# V71_XplainedUltra_CAN_Shield.net
KiCad netlist of a schematic drawn in EasyEDA
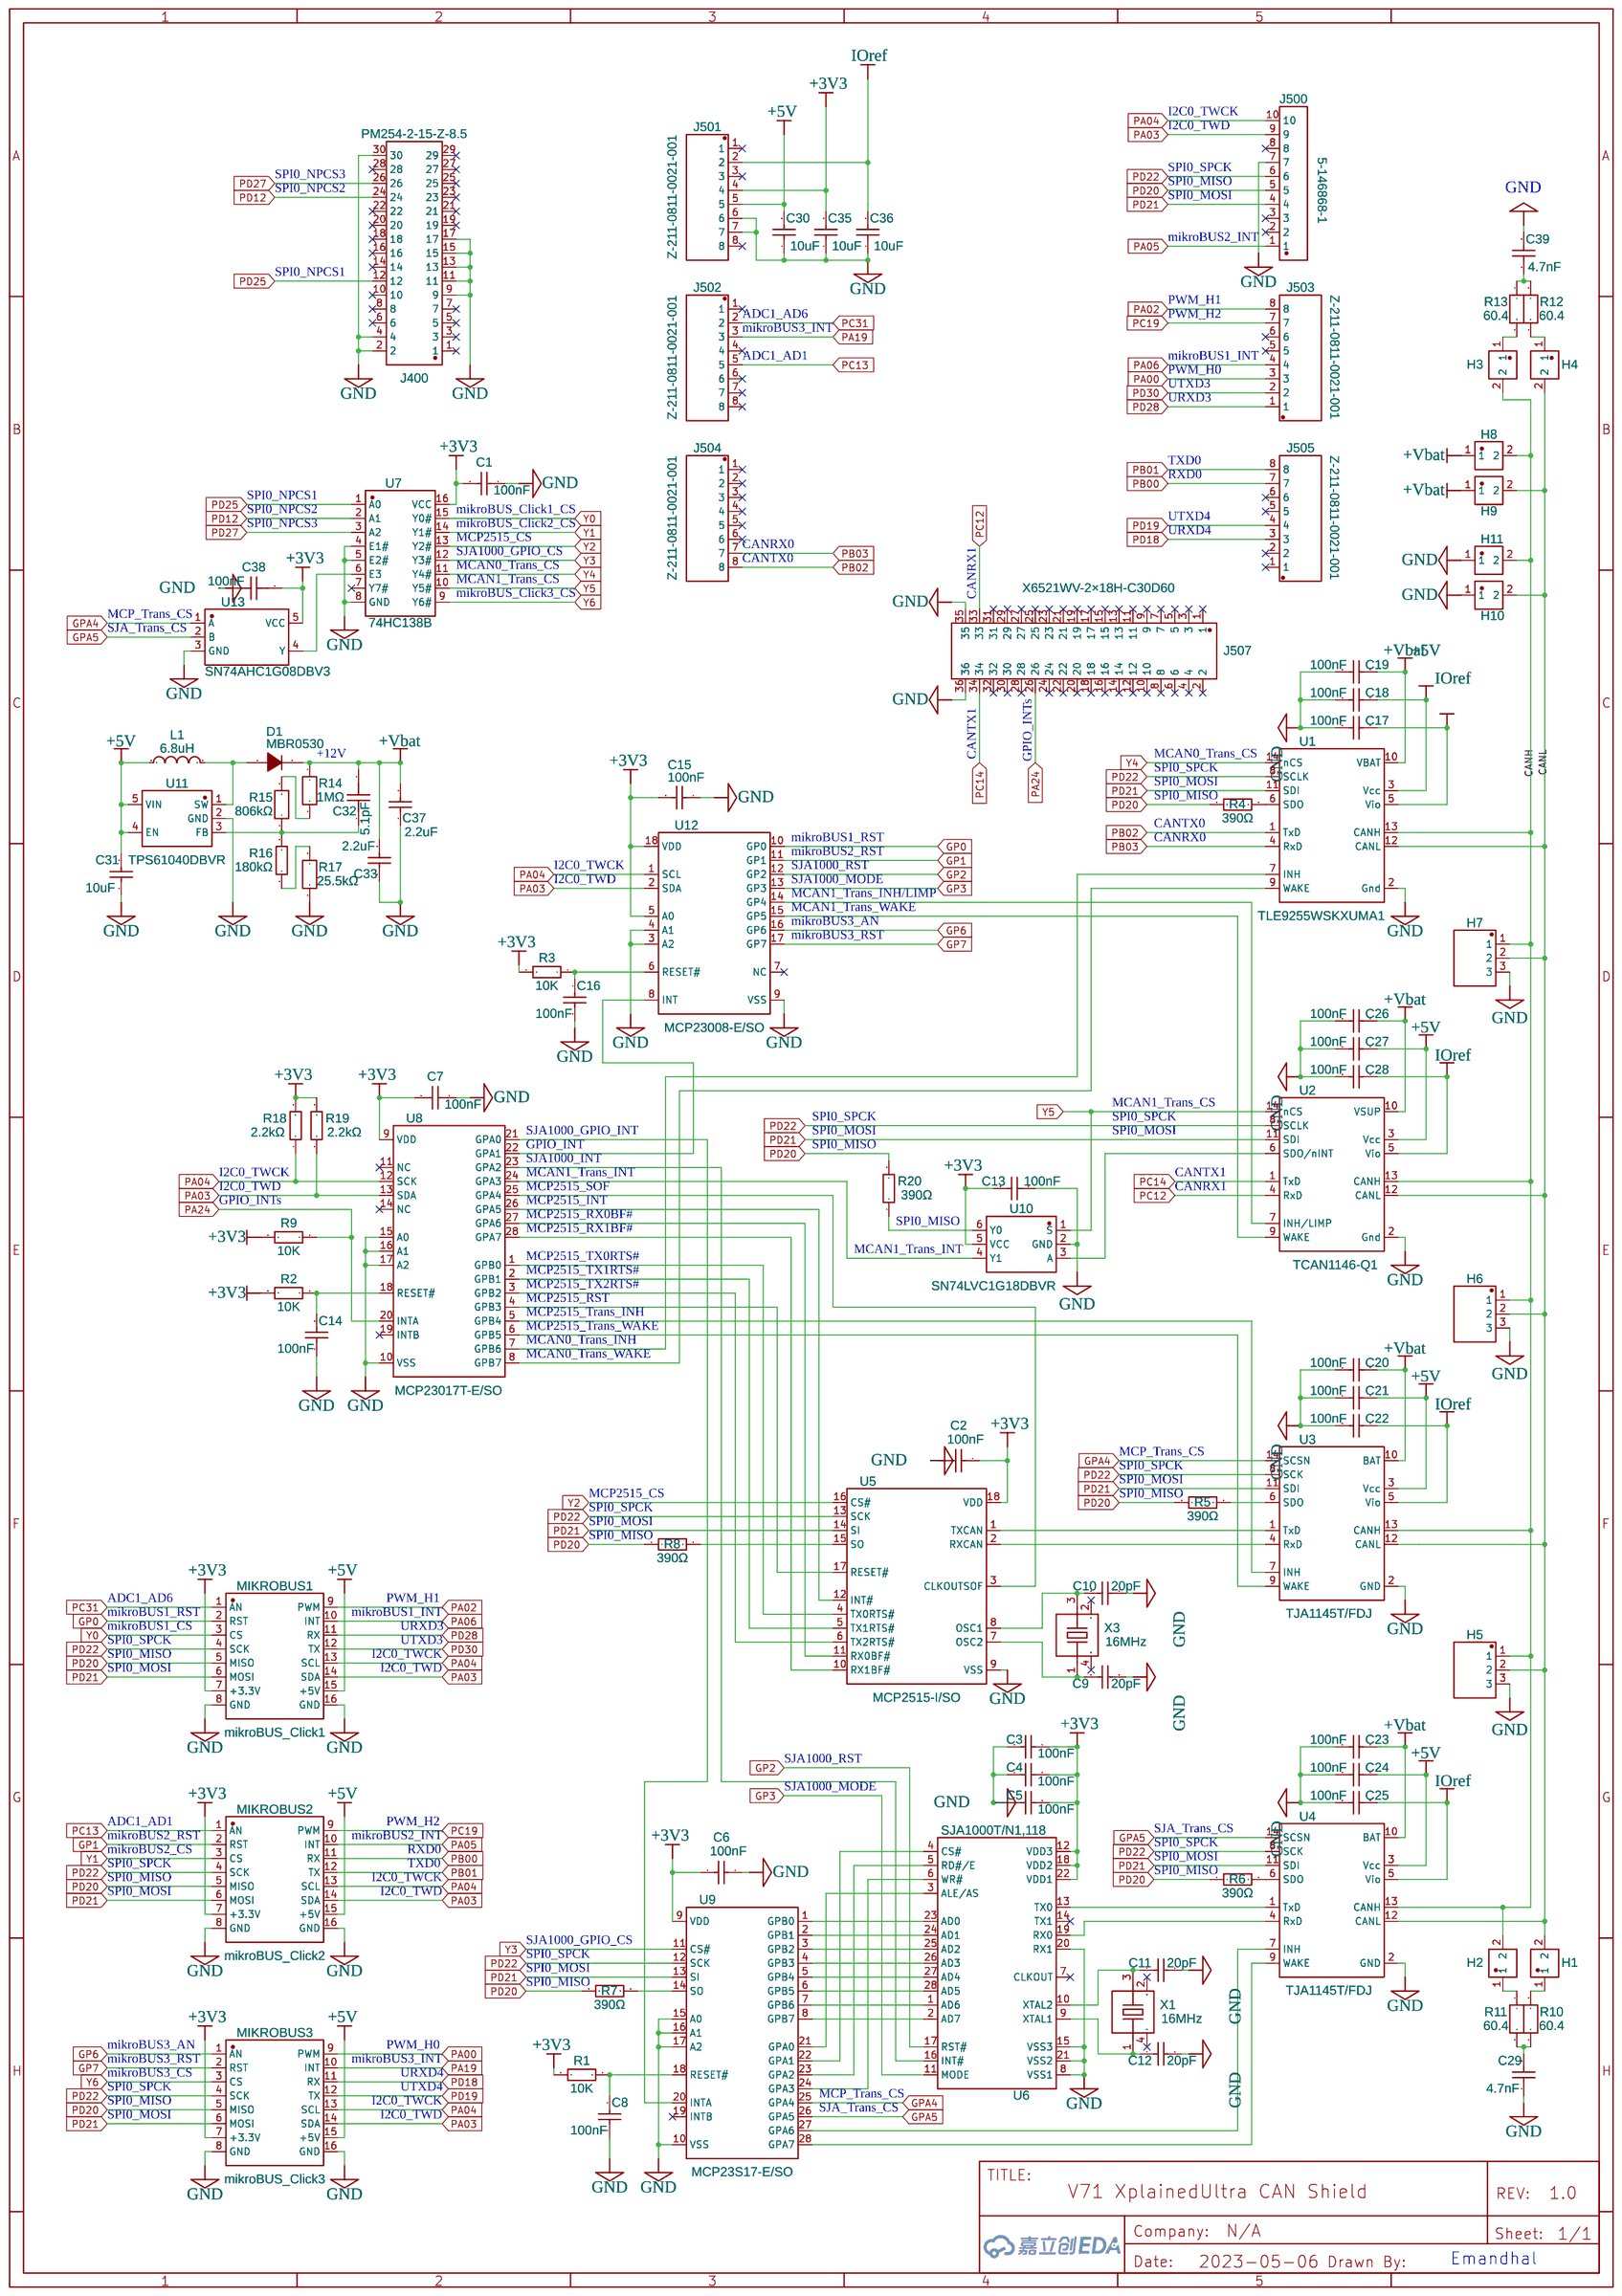
[diagram p0: schematic sheet]

(export (version "E")
  (design (tool "Eeschema 10.0.6"))
  (components
    (comp (ref "C1")
      (value "100nF")
      (fields
        (field (name "Manufacturer Part") "CC0805KRX7R9BB104")
        (field (name "Manufacturer") "YAGEO(国巨)")
      )
      (libsource (lib "") (part "CC0805KRX7R9BB104"))
    )
    (comp (ref "C2")
      (value "100nF")
      (fields
        (field (name "Manufacturer Part") "CC0805KRX7R9BB104")
        (field (name "Manufacturer") "YAGEO(国巨)")
      )
      (libsource (lib "") (part "CC0805KRX7R9BB104"))
    )
    (comp (ref "C3")
      (value "100nF")
      (fields
        (field (name "Manufacturer Part") "CC0805KRX7R9BB104")
        (field (name "Manufacturer") "YAGEO(国巨)")
      )
      (libsource (lib "") (part "CC0805KRX7R9BB104"))
    )
    (comp (ref "C4")
      (value "100nF")
      (fields
        (field (name "Manufacturer Part") "CC0805KRX7R9BB104")
        (field (name "Manufacturer") "YAGEO(国巨)")
      )
      (libsource (lib "") (part "CC0805KRX7R9BB104"))
    )
    (comp (ref "C5")
      (value "100nF")
      (fields
        (field (name "Manufacturer Part") "CC0805KRX7R9BB104")
        (field (name "Manufacturer") "YAGEO(国巨)")
      )
      (libsource (lib "") (part "CC0805KRX7R9BB104"))
    )
    (comp (ref "C6")
      (value "100nF")
      (fields
        (field (name "Manufacturer Part") "CC0805KRX7R9BB104")
        (field (name "Manufacturer") "YAGEO(国巨)")
      )
      (libsource (lib "") (part "CC0805KRX7R9BB104"))
    )
    (comp (ref "C7")
      (value "100nF")
      (fields
        (field (name "Manufacturer Part") "CC0805KRX7R9BB104")
        (field (name "Manufacturer") "YAGEO(国巨)")
      )
      (libsource (lib "") (part "CC0805KRX7R9BB104"))
    )
    (comp (ref "C8")
      (value "100nF")
      (fields
        (field (name "Manufacturer Part") "CC0805KRX7R9BB104")
        (field (name "Manufacturer") "YAGEO(国巨)")
      )
      (libsource (lib "") (part "CC0805KRX7R9BB104_1"))
    )
    (comp (ref "C9")
      (value "20pF")
      (fields
        (field (name "Manufacturer Part") "CL10C200JB8NNNC")
        (field (name "Manufacturer") "SAMSUNG(三星)")
      )
      (libsource (lib "") (part "CL10C200JB8NNNC"))
    )
    (comp (ref "C10")
      (value "20pF")
      (fields
        (field (name "Manufacturer Part") "CL10C200JB8NNNC")
        (field (name "Manufacturer") "SAMSUNG(三星)")
      )
      (libsource (lib "") (part "CL10C200JB8NNNC"))
    )
    (comp (ref "C11")
      (value "20pF")
      (fields
        (field (name "Manufacturer Part") "CL10C200JB8NNNC")
        (field (name "Manufacturer") "SAMSUNG(三星)")
      )
      (libsource (lib "") (part "CL10C200JB8NNNC"))
    )
    (comp (ref "C12")
      (value "20pF")
      (fields
        (field (name "Manufacturer Part") "CL10C200JB8NNNC")
        (field (name "Manufacturer") "SAMSUNG(三星)")
      )
      (libsource (lib "") (part "CL10C200JB8NNNC"))
    )
    (comp (ref "C13")
      (value "100nF")
      (fields
        (field (name "Manufacturer Part") "CC0805KRX7R9BB104")
        (field (name "Manufacturer") "YAGEO(国巨)")
      )
      (libsource (lib "") (part "CC0805KRX7R9BB104"))
    )
    (comp (ref "C14")
      (value "100nF")
      (fields
        (field (name "Manufacturer Part") "CC0805KRX7R9BB104")
        (field (name "Manufacturer") "YAGEO(国巨)")
      )
      (libsource (lib "") (part "CC0805KRX7R9BB104_1"))
    )
    (comp (ref "C15")
      (value "100nF")
      (fields
        (field (name "Manufacturer Part") "CC0805KRX7R9BB104")
        (field (name "Manufacturer") "YAGEO(国巨)")
      )
      (libsource (lib "") (part "CC0805KRX7R9BB104"))
    )
    (comp (ref "C16")
      (value "100nF")
      (fields
        (field (name "Manufacturer Part") "CC0805KRX7R9BB104")
        (field (name "Manufacturer") "YAGEO(国巨)")
      )
      (libsource (lib "") (part "CC0805KRX7R9BB104_1"))
    )
    (comp (ref "C17")
      (value "100nF")
      (fields
        (field (name "Manufacturer Part") "CC0805KRX7R9BB104")
        (field (name "Manufacturer") "YAGEO(国巨)")
      )
      (libsource (lib "") (part "CC0805KRX7R9BB104"))
    )
    (comp (ref "C18")
      (value "100nF")
      (fields
        (field (name "Manufacturer Part") "CC0805KRX7R9BB104")
        (field (name "Manufacturer") "YAGEO(国巨)")
      )
      (libsource (lib "") (part "CC0805KRX7R9BB104"))
    )
    (comp (ref "C19")
      (value "100nF")
      (fields
        (field (name "Manufacturer Part") "CC0805KRX7R9BB104")
        (field (name "Manufacturer") "YAGEO(国巨)")
      )
      (libsource (lib "") (part "CC0805KRX7R9BB104"))
    )
    (comp (ref "C20")
      (value "100nF")
      (fields
        (field (name "Manufacturer Part") "CC0805KRX7R9BB104")
        (field (name "Manufacturer") "YAGEO(国巨)")
      )
      (libsource (lib "") (part "CC0805KRX7R9BB104"))
    )
    (comp (ref "C21")
      (value "100nF")
      (fields
        (field (name "Manufacturer Part") "CC0805KRX7R9BB104")
        (field (name "Manufacturer") "YAGEO(国巨)")
      )
      (libsource (lib "") (part "CC0805KRX7R9BB104"))
    )
    (comp (ref "C22")
      (value "100nF")
      (fields
        (field (name "Manufacturer Part") "CC0805KRX7R9BB104")
        (field (name "Manufacturer") "YAGEO(国巨)")
      )
      (libsource (lib "") (part "CC0805KRX7R9BB104"))
    )
    (comp (ref "C23")
      (value "100nF")
      (fields
        (field (name "Manufacturer Part") "CC0805KRX7R9BB104")
        (field (name "Manufacturer") "YAGEO(国巨)")
      )
      (libsource (lib "") (part "CC0805KRX7R9BB104"))
    )
    (comp (ref "C24")
      (value "100nF")
      (fields
        (field (name "Manufacturer Part") "CC0805KRX7R9BB104")
        (field (name "Manufacturer") "YAGEO(国巨)")
      )
      (libsource (lib "") (part "CC0805KRX7R9BB104"))
    )
    (comp (ref "C25")
      (value "100nF")
      (fields
        (field (name "Manufacturer Part") "CC0805KRX7R9BB104")
        (field (name "Manufacturer") "YAGEO(国巨)")
      )
      (libsource (lib "") (part "CC0805KRX7R9BB104"))
    )
    (comp (ref "C26")
      (value "100nF")
      (fields
        (field (name "Manufacturer Part") "CC0805KRX7R9BB104")
        (field (name "Manufacturer") "YAGEO(国巨)")
      )
      (libsource (lib "") (part "CC0805KRX7R9BB104"))
    )
    (comp (ref "C27")
      (value "100nF")
      (fields
        (field (name "Manufacturer Part") "CC0805KRX7R9BB104")
        (field (name "Manufacturer") "YAGEO(国巨)")
      )
      (libsource (lib "") (part "CC0805KRX7R9BB104"))
    )
    (comp (ref "C28")
      (value "100nF")
      (fields
        (field (name "Manufacturer Part") "CC0805KRX7R9BB104")
        (field (name "Manufacturer") "YAGEO(国巨)")
      )
      (libsource (lib "") (part "CC0805KRX7R9BB104"))
    )
    (comp (ref "C29")
      (value "4.7nF")
      (fields (field (name "Manufacturer Part") "0805B472K500NT") (field (name "Manufacturer") "FH(风华)"))
      (libsource (lib "") (part "0805B472K500NT"))
    )
    (comp (ref "C30")
      (value "10uF")
      (fields
        (field (name "Manufacturer Part") "CL21A106KAYNNNE")
        (field (name "Manufacturer") "SAMSUNG(三星)")
      )
      (libsource (lib "") (part "CL21A106KAYNNNE"))
    )
    (comp (ref "C31")
      (value "10uF")
      (fields
        (field (name "Manufacturer Part") "CL21A106KAYNNNE")
        (field (name "Manufacturer") "SAMSUNG(三星)")
      )
      (libsource (lib "") (part "CL21A106KAYNNNE"))
    )
    (comp (ref "C32")
      (value "5.1pF")
      (fields
        (field (name "Manufacturer Part") "CC0805CRNPO9BN5R1")
        (field (name "Manufacturer") "YAGEO(国巨)")
      )
      (libsource (lib "") (part "CC0805CRNPO9BN5R1"))
    )
    (comp (ref "C33")
      (value "2.2uF")
      (fields (field (name "Manufacturer Part") "0805F225M500NT") (field (name "Manufacturer") "FH(风华)"))
      (libsource (lib "") (part "0805F225M500NT"))
    )
    (comp (ref "C35")
      (value "10uF")
      (fields
        (field (name "Manufacturer Part") "CL21A106KAYNNNE")
        (field (name "Manufacturer") "SAMSUNG(三星)")
      )
      (libsource (lib "") (part "CL21A106KAYNNNE"))
    )
    (comp (ref "C36")
      (value "10uF")
      (fields
        (field (name "Manufacturer Part") "CL21A106KAYNNNE")
        (field (name "Manufacturer") "SAMSUNG(三星)")
      )
      (libsource (lib "") (part "CL21A106KAYNNNE"))
    )
    (comp (ref "C37")
      (value "2.2uF")
      (fields (field (name "Manufacturer Part") "0805F225M500NT") (field (name "Manufacturer") "FH(风华)"))
      (libsource (lib "") (part "0805F225M500NT"))
    )
    (comp (ref "C38")
      (value "100nF")
      (fields
        (field (name "Manufacturer Part") "CC0805KRX7R7BB104")
        (field (name "Manufacturer") "YAGEO(国巨)")
      )
      (libsource (lib "") (part "CC0805KRX7R7BB104"))
    )
    (comp (ref "C39")
      (value "4.7nF")
      (fields (field (name "Manufacturer Part") "0805B472K500NT") (field (name "Manufacturer") "FH(风华)"))
      (libsource (lib "") (part "0805B472K500NT"))
    )
    (comp (ref "D1")
      (value "MBR0530")
      (fields (field (name "Manufacturer") "CJ(江苏长电/长晶)"))
      (libsource (lib "") (part "MBR0530"))
    )
    (comp (ref "H1")
      (value "X6521WV-2X01H-C30D60")
      (fields
        (field (name "Manufacturer Part") "X6521WV-2x01H-C30D60")
        (field (name "Manufacturer") "XKB Connectivity(中国星坤)")
      )
      (libsource (lib "") (part "X6521WV-2X01H-C30D60_2"))
    )
    (comp (ref "H2")
      (value "X6521WV-2X01H-C30D60")
      (fields
        (field (name "Manufacturer Part") "X6521WV-2x01H-C30D60")
        (field (name "Manufacturer") "XKB Connectivity(中国星坤)")
      )
      (libsource (lib "") (part "X6521WV-2X01H-C30D60_2"))
    )
    (comp (ref "H3")
      (value "X6521WV-2X01H-C30D60")
      (fields
        (field (name "Manufacturer Part") "X6521WV-2x01H-C30D60")
        (field (name "Manufacturer") "XKB Connectivity(中国星坤)")
      )
      (libsource (lib "") (part "X6521WV-2X01H-C30D60"))
    )
    (comp (ref "H4")
      (value "X6521WV-2X01H-C30D60")
      (fields
        (field (name "Manufacturer Part") "X6521WV-2x01H-C30D60")
        (field (name "Manufacturer") "XKB Connectivity(中国星坤)")
      )
      (libsource (lib "") (part "X6521WV-2X01H-C30D60"))
    )
    (comp (ref "H5")
      (value "77311-102-03LF")
      (fields (field (name "Manufacturer") "Amphenol"))
      (libsource (lib "") (part "77311-102-03LF"))
    )
    (comp (ref "H6")
      (value "77311-102-03LF")
      (fields (field (name "Manufacturer") "Amphenol"))
      (libsource (lib "") (part "77311-102-03LF"))
    )
    (comp (ref "H7")
      (value "77311-102-03LF")
      (fields (field (name "Manufacturer") "Amphenol"))
      (libsource (lib "") (part "77311-102-03LF"))
    )
    (comp (ref "H8")
      (value "X6521WV-2X01H-C30D60")
      (fields
        (field (name "Manufacturer Part") "X6521WV-2x01H-C30D60")
        (field (name "Manufacturer") "XKB Connectivity(中国星坤)")
      )
      (libsource (lib "") (part "X6521WV-2X01H-C30D60_1"))
    )
    (comp (ref "H9")
      (value "X6521WV-2X01H-C30D60")
      (fields
        (field (name "Manufacturer Part") "X6521WV-2x01H-C30D60")
        (field (name "Manufacturer") "XKB Connectivity(中国星坤)")
      )
      (libsource (lib "") (part "X6521WV-2X01H-C30D60_1"))
    )
    (comp (ref "H10")
      (value "X6521WV-2X01H-C30D60")
      (fields
        (field (name "Manufacturer Part") "X6521WV-2x01H-C30D60")
        (field (name "Manufacturer") "XKB Connectivity(中国星坤)")
      )
      (libsource (lib "") (part "X6521WV-2X01H-C30D60_1"))
    )
    (comp (ref "H11")
      (value "X6521WV-2X01H-C30D60")
      (fields
        (field (name "Manufacturer Part") "X6521WV-2x01H-C30D60")
        (field (name "Manufacturer") "XKB Connectivity(中国星坤)")
      )
      (libsource (lib "") (part "X6521WV-2X01H-C30D60_1"))
    )
    (comp (ref "J400")
      (value "PM254-2-15-Z-8.5")
      (fields (field (name "Manufacturer") "HCTL(华灿天禄)"))
      (libsource (lib "") (part "PM254-2-15-Z-8.5"))
    )
    (comp (ref "J500")
      (value "5-146868-1")
      (fields (field (name "Manufacturer") "TE Connectivity(美国泰科)"))
      (libsource (lib "") (part "5-146868-1"))
    )
    (comp (ref "J501")
      (value "Z-211-0811-0021-001")
      (fields (field (name "Manufacturer") "Nextron(正凌)"))
      (libsource (lib "") (part "Z-211-0811-0021-001"))
    )
    (comp (ref "J502")
      (value "Z-211-0811-0021-001")
      (fields (field (name "Manufacturer") "Nextron(正凌)"))
      (libsource (lib "") (part "Z-211-0811-0021-001"))
    )
    (comp (ref "J503")
      (value "Z-211-0811-0021-001")
      (fields (field (name "Manufacturer") "Nextron(正凌)"))
      (libsource (lib "") (part "Z-211-0811-0021-001_1"))
    )
    (comp (ref "J504")
      (value "Z-211-0811-0021-001")
      (fields (field (name "Manufacturer") "Nextron(正凌)"))
      (libsource (lib "") (part "Z-211-0811-0021-001"))
    )
    (comp (ref "J505")
      (value "Z-211-0811-0021-001")
      (fields (field (name "Manufacturer") "Nextron(正凌)"))
      (libsource (lib "") (part "Z-211-0811-0021-001_1"))
    )
    (comp (ref "J507")
      (value "X6521WV-2×18H-C30D60")
      (fields
        (field (name "Manufacturer Part") "X6521WV-2x18H-C30D60")
        (field (name "Manufacturer") "XKB Connectivity(中国星坤)")
      )
      (libsource (lib "") (part "X6521WV-2×18H-C30D60"))
    )
    (comp (ref "L1")
      (value "6.8uH")
      (fields (field (name "Manufacturer Part") "MLZ2012N6R8LT000") (field (name "Manufacturer") "TDK"))
      (libsource (lib "") (part "MLZ2012N6R8LT000"))
    )
    (comp (ref "MIKROBUS1") (value "mikroBUS_Click1") (libsource (lib "") (part "MIKROE-CLICK-HEADER")))
    (comp (ref "MIKROBUS2") (value "mikroBUS_Click2") (libsource (lib "") (part "MIKROE-CLICK-HEADER")))
    (comp (ref "MIKROBUS3") (value "mikroBUS_Click3") (libsource (lib "") (part "MIKROE-CLICK-HEADER")))
    (comp (ref "R1")
      (value "10K")
      (fields (field (name "Manufacturer Part") "RT0805BRD0710KL") (field (name "Manufacturer") "YAGEO(国巨)"))
      (libsource (lib "") (part "RT0805BRD0710KL"))
    )
    (comp (ref "R2")
      (value "10K")
      (fields (field (name "Manufacturer Part") "RT0805BRD0710KL") (field (name "Manufacturer") "YAGEO(国巨)"))
      (libsource (lib "") (part "RT0805BRD0710KL"))
    )
    (comp (ref "R3")
      (value "10K")
      (fields (field (name "Manufacturer Part") "RT0805BRD0710KL") (field (name "Manufacturer") "YAGEO(国巨)"))
      (libsource (lib "") (part "RT0805BRD0710KL"))
    )
    (comp (ref "R4")
      (value "390Ω")
      (fields
        (field (name "Manufacturer Part") "0805W8F3900T5E")
        (field (name "Manufacturer") "UNI-ROYAL(厚声)")
      )
      (libsource (lib "") (part "0805W8F3900T5E"))
    )
    (comp (ref "R5")
      (value "390Ω")
      (fields
        (field (name "Manufacturer Part") "0805W8F3900T5E")
        (field (name "Manufacturer") "UNI-ROYAL(厚声)")
      )
      (libsource (lib "") (part "0805W8F3900T5E"))
    )
    (comp (ref "R6")
      (value "390Ω")
      (fields
        (field (name "Manufacturer Part") "0805W8F3900T5E")
        (field (name "Manufacturer") "UNI-ROYAL(厚声)")
      )
      (libsource (lib "") (part "0805W8F3900T5E"))
    )
    (comp (ref "R7")
      (value "390Ω")
      (fields
        (field (name "Manufacturer Part") "0805W8F3900T5E")
        (field (name "Manufacturer") "UNI-ROYAL(厚声)")
      )
      (libsource (lib "") (part "0805W8F3900T5E"))
    )
    (comp (ref "R8")
      (value "390Ω")
      (fields
        (field (name "Manufacturer Part") "0805W8F3900T5E")
        (field (name "Manufacturer") "UNI-ROYAL(厚声)")
      )
      (libsource (lib "") (part "0805W8F3900T5E"))
    )
    (comp (ref "R9")
      (value "10K")
      (fields (field (name "Manufacturer Part") "RT0805BRD0710KL") (field (name "Manufacturer") "YAGEO(国巨)"))
      (libsource (lib "") (part "RT0805BRD0710KL"))
    )
    (comp (ref "R10")
      (value "60.4")
      (fields (field (name "Manufacturer Part") "AC0603DR-0760R4L") (field (name "Manufacturer") "YAGEO(国巨)"))
      (libsource (lib "") (part "AC0603DR-0760R4L_1"))
    )
    (comp (ref "R11")
      (value "60.4")
      (fields (field (name "Manufacturer Part") "AC0603DR-0760R4L") (field (name "Manufacturer") "YAGEO(国巨)"))
      (libsource (lib "") (part "AC0603DR-0760R4L"))
    )
    (comp (ref "R12")
      (value "60.4")
      (fields (field (name "Manufacturer Part") "AC0603DR-0760R4L") (field (name "Manufacturer") "YAGEO(国巨)"))
      (libsource (lib "") (part "AC0603DR-0760R4L_1"))
    )
    (comp (ref "R13")
      (value "60.4")
      (fields (field (name "Manufacturer Part") "AC0603DR-0760R4L") (field (name "Manufacturer") "YAGEO(国巨)"))
      (libsource (lib "") (part "AC0603DR-0760R4L"))
    )
    (comp (ref "R14")
      (value "1MΩ")
      (fields (field (name "Manufacturer Part") "CR-05FL7----1M") (field (name "Manufacturer") "Viking(光颉)"))
      (libsource (lib "") (part "CR-05FL7----1M"))
    )
    (comp (ref "R15")
      (value "806kΩ")
      (fields (field (name "Manufacturer Part") "WR08X8063FTL") (field (name "Manufacturer") "Walsin(华新科)"))
      (libsource (lib "") (part "WR08X8063FTL"))
    )
    (comp (ref "R16")
      (value "180kΩ")
      (fields (field (name "Manufacturer Part") "RK73B2ATTD184J") (field (name "Manufacturer") "KOA"))
      (libsource (lib "") (part "RK73B2ATTD184J"))
    )
    (comp (ref "R17")
      (value "25.5kΩ")
      (fields (field (name "Manufacturer Part") "TE05H2552BT") (field (name "Manufacturer") "FH(风华)"))
      (libsource (lib "") (part "TE05H2552BT"))
    )
    (comp (ref "R18")
      (value "2.2kΩ")
      (fields (field (name "Manufacturer Part") "AR05BTB2201") (field (name "Manufacturer") "Viking(光颉)"))
      (libsource (lib "") (part "AR05BTB2201"))
    )
    (comp (ref "R19")
      (value "2.2kΩ")
      (fields (field (name "Manufacturer Part") "AR05BTB2201") (field (name "Manufacturer") "Viking(光颉)"))
      (libsource (lib "") (part "AR05BTB2201"))
    )
    (comp (ref "R20")
      (value "390Ω")
      (fields
        (field (name "Manufacturer Part") "0805W8F3900T5E")
        (field (name "Manufacturer") "UNI-ROYAL(厚声)")
      )
      (libsource (lib "") (part "0805W8F3900T5E_1"))
    )
    (comp (ref "U1")
      (value "TLE9255WSKXUMA1")
      (fields (field (name "Manufacturer") "Infineon(英飞凌)"))
      (libsource (lib "") (part "TLE9255WSKXUMA1"))
    )
    (comp (ref "U2")
      (value "TCAN1146-Q1")
      (fields
        (field (name "Manufacturer Part") "TCAN1146D-Q1")
        (field (name "Manufacturer") "Texas Instruments")
      )
      (libsource (lib "") (part "TCAN1146-Q1"))
    )
    (comp (ref "U3")
      (value "TJA1145T/FDJ")
      (fields (field (name "Manufacturer") "NXP(恩智浦)"))
      (libsource (lib "") (part "TJA1145T/FDJ"))
    )
    (comp (ref "U4")
      (value "TJA1145T/FDJ")
      (fields (field (name "Manufacturer") "NXP(恩智浦)"))
      (libsource (lib "") (part "TJA1145T/FDJ"))
    )
    (comp (ref "U5")
      (value "MCP2515-I/SO")
      (fields (field (name "Manufacturer") "MICROCHIP(美国微芯)"))
      (libsource (lib "") (part "MCP2515-I/SO"))
    )
    (comp (ref "U6")
      (value "SJA1000T/N1,118")
      (fields (field (name "Manufacturer") "NXP(恩智浦)"))
      (libsource (lib "") (part "SJA1000T/N1,118"))
    )
    (comp (ref "U7")
      (value "74HC138B")
      (fields (field (name "Manufacturer") "FM(富满)"))
      (libsource (lib "") (part "74HC138B"))
    )
    (comp (ref "U8")
      (value "MCP23017T-E/SO")
      (fields (field (name "Manufacturer") "MICROCHIP(美国微芯)"))
      (libsource (lib "") (part "MCP23017T-E/SO"))
    )
    (comp (ref "U9")
      (value "MCP23S17-E/SO")
      (fields (field (name "Manufacturer") "MICROCHIP(美国微芯)"))
      (libsource (lib "") (part "MCP23S17-E/SO"))
    )
    (comp (ref "U10")
      (value "SN74LVC1G18DBVR")
      (fields (field (name "Manufacturer") "TI(德州仪器)"))
      (libsource (lib "") (part "SN74LVC1G18DBVR"))
    )
    (comp (ref "U11")
      (value "TPS61040DBVR")
      (fields (field (name "Manufacturer") "TI(德州仪器)"))
      (libsource (lib "") (part "TPS61040DBVR"))
    )
    (comp (ref "U12")
      (value "MCP23008-E/SO")
      (fields (field (name "Manufacturer") "MICROCHIP(美国微芯)"))
      (libsource (lib "") (part "MCP23008-E/SO"))
    )
    (comp (ref "U13")
      (value "SN74AHC1G08DBV3")
      (fields (field (name "Manufacturer") "TI(德州仪器)"))
      (libsource (lib "") (part "SN74AHC1G08DBV3"))
    )
    (comp (ref "X1")
      (value "16MHz")
      (fields
        (field (name "Manufacturer Part") "NX3225SA-16MHz-STD-CSR-6")
        (field (name "Manufacturer") "NDK")
      )
      (libsource (lib "") (part "NX3225SA-16MHZ-STD-CSR-6"))
    )
    (comp (ref "X3")
      (value "16MHz")
      (fields
        (field (name "Manufacturer Part") "NX3225SA-16MHz-STD-CSR-6")
        (field (name "Manufacturer") "NDK")
      )
      (libsource (lib "") (part "NX3225SA-16MHZ-STD-CSR-6"))
    )
  )
  (nets
    (net (code "1") (name "+3V3") (class "Default")
      (node (ref "C1") (pin "2") (pinfunction "2_2") (pintype "input"))
      (node (ref "C13") (pin "2") (pinfunction "2_2") (pintype "input"))
      (node (ref "C15") (pin "2") (pinfunction "2_2") (pintype "input"))
      (node (ref "C2") (pin "1") (pinfunction "1_1") (pintype "input"))
      (node (ref "C3") (pin "1") (pinfunction "1_1") (pintype "input"))
      (node (ref "C35") (pin "2") (pinfunction "2_2") (pintype "input"))
      (node (ref "C38") (pin "1") (pinfunction "1_1") (pintype "unspecified"))
      (node (ref "C4") (pin "1") (pinfunction "1_1") (pintype "input"))
      (node (ref "C5") (pin "1") (pinfunction "1_1") (pintype "input"))
      (node (ref "C6") (pin "2") (pinfunction "2_2") (pintype "input"))
      (node (ref "C7") (pin "2") (pinfunction "2_2") (pintype "input"))
      (node (ref "J501") (pin "4") (pinfunction "4_4") (pintype "unspecified"))
      (node (ref "MIKROBUS1") (pin "7") (pinfunction "+3.3V_7") (pintype "unspecified"))
      (node (ref "MIKROBUS2") (pin "7") (pinfunction "+3.3V_7") (pintype "unspecified"))
      (node (ref "MIKROBUS3") (pin "7") (pinfunction "+3.3V_7") (pintype "unspecified"))
      (node (ref "R1") (pin "2") (pinfunction "2_2") (pintype "input"))
      (node (ref "R18") (pin "2") (pinfunction "2_2") (pintype "unspecified"))
      (node (ref "R19") (pin "2") (pinfunction "2_2") (pintype "unspecified"))
      (node (ref "R2") (pin "2") (pinfunction "2_2") (pintype "input"))
      (node (ref "R3") (pin "2") (pinfunction "2_2") (pintype "input"))
      (node (ref "R9") (pin "2") (pinfunction "2_2") (pintype "input"))
      (node (ref "U10") (pin "5") (pinfunction "VCC_5") (pintype "unspecified"))
      (node (ref "U12") (pin "18") (pinfunction "VDD_18") (pintype "passive"))
      (node (ref "U12") (pin "5") (pinfunction "A0_5") (pintype "input"))
      (node (ref "U13") (pin "5") (pinfunction "VCC_5") (pintype "unspecified"))
      (node (ref "U5") (pin "18") (pinfunction "VDD_18") (pintype "unspecified"))
      (node (ref "U6") (pin "12") (pinfunction "VDD3_12") (pintype "unspecified"))
      (node (ref "U6") (pin "18") (pinfunction "VDD2_18") (pintype "unspecified"))
      (node (ref "U6") (pin "22") (pinfunction "VDD1_22") (pintype "unspecified"))
      (node (ref "U7") (pin "16") (pinfunction "VCC_16") (pintype "unspecified"))
      (node (ref "U8") (pin "9") (pinfunction "VDD_9") (pintype "passive"))
      (node (ref "U9") (pin "9") (pinfunction "VDD_9") (pintype "passive"))
    )
    (net (code "2") (name "+5V") (class "Default")
      (node (ref "C18") (pin "1") (pinfunction "1_1") (pintype "input"))
      (node (ref "C21") (pin "1") (pinfunction "1_1") (pintype "input"))
      (node (ref "C24") (pin "1") (pinfunction "1_1") (pintype "input"))
      (node (ref "C27") (pin "1") (pinfunction "1_1") (pintype "input"))
      (node (ref "C30") (pin "2") (pinfunction "2_2") (pintype "input"))
      (node (ref "C31") (pin "2") (pinfunction "2_2") (pintype "input"))
      (node (ref "J501") (pin "5") (pinfunction "5_5") (pintype "unspecified"))
      (node (ref "L1") (pin "1") (pinfunction "1_1") (pintype "unspecified"))
      (node (ref "MIKROBUS1") (pin "15") (pinfunction "+5V_15") (pintype "unspecified"))
      (node (ref "MIKROBUS2") (pin "15") (pinfunction "+5V_15") (pintype "unspecified"))
      (node (ref "MIKROBUS3") (pin "15") (pinfunction "+5V_15") (pintype "unspecified"))
      (node (ref "U1") (pin "3") (pinfunction "Vcc_3") (pintype "unspecified"))
      (node (ref "U11") (pin "4") (pinfunction "EN_4") (pintype "unspecified"))
      (node (ref "U11") (pin "5") (pinfunction "VIN_5") (pintype "unspecified"))
      (node (ref "U2") (pin "3") (pinfunction "Vcc_3") (pintype "unspecified"))
      (node (ref "U3") (pin "3") (pinfunction "Vcc_3") (pintype "unspecified"))
      (node (ref "U4") (pin "3") (pinfunction "Vcc_3") (pintype "unspecified"))
    )
    (net (code "3") (name "+Vbat") (class "Default")
      (node (ref "C19") (pin "1") (pinfunction "1_1") (pintype "input"))
      (node (ref "C20") (pin "1") (pinfunction "1_1") (pintype "input"))
      (node (ref "C23") (pin "1") (pinfunction "1_1") (pintype "input"))
      (node (ref "C26") (pin "1") (pinfunction "1_1") (pintype "input"))
      (node (ref "C32") (pin "2") (pinfunction "2_2") (pintype "unspecified"))
      (node (ref "C33") (pin "2") (pinfunction "2_2") (pintype "input"))
      (node (ref "C37") (pin "2") (pinfunction "2_2") (pintype "input"))
      (node (ref "D1") (pin "1") (pinfunction "C_1") (pintype "unspecified"))
      (node (ref "H8") (pin "1") (pinfunction "1_1") (pintype "unspecified"))
      (node (ref "H9") (pin "1") (pinfunction "1_1") (pintype "unspecified"))
      (node (ref "R14") (pin "2") (pinfunction "2_2") (pintype "unspecified"))
      (node (ref "U1") (pin "10") (pinfunction "VBAT_10") (pintype "unspecified"))
      (node (ref "U2") (pin "10") (pinfunction "VSUP_10") (pintype "unspecified"))
      (node (ref "U3") (pin "10") (pinfunction "BAT_10") (pintype "unspecified"))
      (node (ref "U4") (pin "10") (pinfunction "BAT_10") (pintype "unspecified"))
    )
    (net (code "4") (name "/CANH") (class "Default")
      (node (ref "H11") (pin "2") (pinfunction "2_2") (pintype "unspecified"))
      (node (ref "H2") (pin "2") (pinfunction "2_2") (pintype "unspecified"))
      (node (ref "H3") (pin "2") (pinfunction "2_2") (pintype "unspecified"))
      (node (ref "H5") (pin "1") (pinfunction "1_1") (pintype "unspecified"))
      (node (ref "H6") (pin "1") (pinfunction "1_1") (pintype "unspecified"))
      (node (ref "H7") (pin "1") (pinfunction "1_1") (pintype "unspecified"))
      (node (ref "H8") (pin "2") (pinfunction "2_2") (pintype "unspecified"))
      (node (ref "U1") (pin "13") (pinfunction "CANH_13") (pintype "unspecified"))
      (node (ref "U2") (pin "13") (pinfunction "CANH_13") (pintype "unspecified"))
      (node (ref "U3") (pin "13") (pinfunction "CANH_13") (pintype "unspecified"))
      (node (ref "U4") (pin "13") (pinfunction "CANH_13") (pintype "unspecified"))
    )
    (net (code "5") (name "/CANL") (class "Default")
      (node (ref "H1") (pin "2") (pinfunction "2_2") (pintype "unspecified"))
      (node (ref "H10") (pin "2") (pinfunction "2_2") (pintype "unspecified"))
      (node (ref "H4") (pin "2") (pinfunction "2_2") (pintype "unspecified"))
      (node (ref "H5") (pin "2") (pinfunction "2_2") (pintype "unspecified"))
      (node (ref "H6") (pin "2") (pinfunction "2_2") (pintype "unspecified"))
      (node (ref "H7") (pin "2") (pinfunction "2_2") (pintype "unspecified"))
      (node (ref "H9") (pin "2") (pinfunction "2_2") (pintype "unspecified"))
      (node (ref "U1") (pin "12") (pinfunction "CANL_12") (pintype "unspecified"))
      (node (ref "U2") (pin "12") (pinfunction "CANL_12") (pintype "unspecified"))
      (node (ref "U3") (pin "12") (pinfunction "CANL_12") (pintype "unspecified"))
      (node (ref "U4") (pin "12") (pinfunction "CANL_12") (pintype "unspecified"))
    )
    (net (code "6") (name "GND") (class "Default")
      (node (ref "C1") (pin "1") (pinfunction "1_1") (pintype "input"))
      (node (ref "C10") (pin "2") (pinfunction "2_2") (pintype "input"))
      (node (ref "C11") (pin "2") (pinfunction "2_2") (pintype "input"))
      (node (ref "C12") (pin "2") (pinfunction "2_2") (pintype "input"))
      (node (ref "C13") (pin "1") (pinfunction "1_1") (pintype "input"))
      (node (ref "C14") (pin "1") (pinfunction "1_1") (pintype "input"))
      (node (ref "C15") (pin "1") (pinfunction "1_1") (pintype "input"))
      (node (ref "C16") (pin "1") (pinfunction "1_1") (pintype "input"))
      (node (ref "C17") (pin "2") (pinfunction "2_2") (pintype "input"))
      (node (ref "C18") (pin "2") (pinfunction "2_2") (pintype "input"))
      (node (ref "C19") (pin "2") (pinfunction "2_2") (pintype "input"))
      (node (ref "C2") (pin "2") (pinfunction "2_2") (pintype "input"))
      (node (ref "C20") (pin "2") (pinfunction "2_2") (pintype "input"))
      (node (ref "C21") (pin "2") (pinfunction "2_2") (pintype "input"))
      (node (ref "C22") (pin "2") (pinfunction "2_2") (pintype "input"))
      (node (ref "C23") (pin "2") (pinfunction "2_2") (pintype "input"))
      (node (ref "C24") (pin "2") (pinfunction "2_2") (pintype "input"))
      (node (ref "C25") (pin "2") (pinfunction "2_2") (pintype "input"))
      (node (ref "C26") (pin "2") (pinfunction "2_2") (pintype "input"))
      (node (ref "C27") (pin "2") (pinfunction "2_2") (pintype "input"))
      (node (ref "C28") (pin "2") (pinfunction "2_2") (pintype "input"))
      (node (ref "C29") (pin "1") (pinfunction "1_1") (pintype "input"))
      (node (ref "C3") (pin "2") (pinfunction "2_2") (pintype "input"))
      (node (ref "C30") (pin "1") (pinfunction "1_1") (pintype "input"))
      (node (ref "C31") (pin "1") (pinfunction "1_1") (pintype "input"))
      (node (ref "C33") (pin "1") (pinfunction "1_1") (pintype "input"))
      (node (ref "C35") (pin "1") (pinfunction "1_1") (pintype "input"))
      (node (ref "C36") (pin "1") (pinfunction "1_1") (pintype "input"))
      (node (ref "C37") (pin "1") (pinfunction "1_1") (pintype "input"))
      (node (ref "C38") (pin "2") (pinfunction "2_2") (pintype "unspecified"))
      (node (ref "C39") (pin "2") (pinfunction "2_2") (pintype "input"))
      (node (ref "C4") (pin "2") (pinfunction "2_2") (pintype "input"))
      (node (ref "C5") (pin "2") (pinfunction "2_2") (pintype "input"))
      (node (ref "C6") (pin "1") (pinfunction "1_1") (pintype "input"))
      (node (ref "C7") (pin "1") (pinfunction "1_1") (pintype "input"))
      (node (ref "C8") (pin "1") (pinfunction "1_1") (pintype "input"))
      (node (ref "C9") (pin "2") (pinfunction "2_2") (pintype "input"))
      (node (ref "H10") (pin "1") (pinfunction "1_1") (pintype "unspecified"))
      (node (ref "H11") (pin "1") (pinfunction "1_1") (pintype "unspecified"))
      (node (ref "H5") (pin "3") (pinfunction "3_3") (pintype "unspecified"))
      (node (ref "H6") (pin "3") (pinfunction "3_3") (pintype "unspecified"))
      (node (ref "H7") (pin "3") (pinfunction "3_3") (pintype "unspecified"))
      (node (ref "J400") (pin "11") (pinfunction "11_11") (pintype "unspecified"))
      (node (ref "J400") (pin "13") (pinfunction "13_13") (pintype "unspecified"))
      (node (ref "J400") (pin "15") (pinfunction "15_15") (pintype "unspecified"))
      (node (ref "J400") (pin "17") (pinfunction "17_17") (pintype "unspecified"))
      (node (ref "J400") (pin "2") (pinfunction "2_2") (pintype "unspecified"))
      (node (ref "J400") (pin "30") (pinfunction "30_30") (pintype "unspecified"))
      (node (ref "J400") (pin "4") (pinfunction "4_4") (pintype "unspecified"))
      (node (ref "J400") (pin "9") (pinfunction "9_9") (pintype "unspecified"))
      (node (ref "J500") (pin "7") (pinfunction "7_7") (pintype "unspecified"))
      (node (ref "J501") (pin "6") (pinfunction "6_6") (pintype "unspecified"))
      (node (ref "J501") (pin "7") (pinfunction "7_7") (pintype "unspecified"))
      (node (ref "J507") (pin "35") (pinfunction "35_35") (pintype "unspecified"))
      (node (ref "J507") (pin "36") (pinfunction "36_36") (pintype "unspecified"))
      (node (ref "MIKROBUS1") (pin "16") (pinfunction "GND_16") (pintype "unspecified"))
      (node (ref "MIKROBUS1") (pin "8") (pinfunction "GND_8") (pintype "unspecified"))
      (node (ref "MIKROBUS2") (pin "16") (pinfunction "GND_16") (pintype "unspecified"))
      (node (ref "MIKROBUS2") (pin "8") (pinfunction "GND_8") (pintype "unspecified"))
      (node (ref "MIKROBUS3") (pin "16") (pinfunction "GND_16") (pintype "unspecified"))
      (node (ref "MIKROBUS3") (pin "8") (pinfunction "GND_8") (pintype "unspecified"))
      (node (ref "R17") (pin "1") (pinfunction "1_1") (pintype "unspecified"))
      (node (ref "U1") (pin "2") (pinfunction "Gnd_2") (pintype "unspecified"))
      (node (ref "U10") (pin "2") (pinfunction "GND_2") (pintype "unspecified"))
      (node (ref "U11") (pin "2") (pinfunction "GND_2") (pintype "unspecified"))
      (node (ref "U12") (pin "3") (pinfunction "A2_3") (pintype "input"))
      (node (ref "U12") (pin "4") (pinfunction "A1_4") (pintype "input"))
      (node (ref "U12") (pin "9") (pinfunction "VSS_9") (pintype "passive"))
      (node (ref "U13") (pin "3") (pinfunction "GND_3") (pintype "unspecified"))
      (node (ref "U2") (pin "2") (pinfunction "Gnd_2") (pintype "unspecified"))
      (node (ref "U3") (pin "2") (pinfunction "GND_2") (pintype "unspecified"))
      (node (ref "U4") (pin "2") (pinfunction "GND_2") (pintype "unspecified"))
      (node (ref "U5") (pin "9") (pinfunction "VSS_9") (pintype "unspecified"))
      (node (ref "U6") (pin "15") (pinfunction "VSS3_15") (pintype "unspecified"))
      (node (ref "U6") (pin "20") (pinfunction "RX1_20") (pintype "unspecified"))
      (node (ref "U6") (pin "21") (pinfunction "VSS2_21") (pintype "unspecified"))
      (node (ref "U6") (pin "8") (pinfunction "VSS1_8") (pintype "unspecified"))
      (node (ref "U7") (pin "4") (pinfunction "E1#_4") (pintype "unspecified"))
      (node (ref "U7") (pin "5") (pinfunction "E2#_5") (pintype "unspecified"))
      (node (ref "U7") (pin "8") (pinfunction "GND_8") (pintype "unspecified"))
      (node (ref "U8") (pin "10") (pinfunction "VSS_10") (pintype "passive"))
      (node (ref "U8") (pin "15") (pinfunction "A0_15") (pintype "unspecified"))
      (node (ref "U8") (pin "16") (pinfunction "A1_16") (pintype "unspecified"))
      (node (ref "U8") (pin "17") (pinfunction "A2_17") (pintype "unspecified"))
      (node (ref "U9") (pin "10") (pinfunction "VSS_10") (pintype "passive"))
      (node (ref "U9") (pin "15") (pinfunction "A0_15") (pintype "unspecified"))
      (node (ref "U9") (pin "16") (pinfunction "A1_16") (pintype "unspecified"))
      (node (ref "U9") (pin "17") (pinfunction "A2_17") (pintype "unspecified"))
    )
    (net (code "7") (name "GP0") (class "Default")
      (node (ref "MIKROBUS1") (pin "2") (pinfunction "RST_2") (pintype "unspecified"))
      (node (ref "U12") (pin "10") (pinfunction "GP0_10") (pintype "unspecified"))
    )
    (net (code "8") (name "GP1") (class "Default")
      (node (ref "MIKROBUS2") (pin "2") (pinfunction "RST_2") (pintype "unspecified"))
      (node (ref "U12") (pin "11") (pinfunction "GP1_11") (pintype "unspecified"))
    )
    (net (code "9") (name "GP2") (class "Default")
      (node (ref "U12") (pin "12") (pinfunction "GP2_12") (pintype "unspecified"))
      (node (ref "U6") (pin "17") (pinfunction "RST#_17") (pintype "unspecified"))
    )
    (net (code "10") (name "GP3") (class "Default")
      (node (ref "U12") (pin "13") (pinfunction "GP3_13") (pintype "unspecified"))
      (node (ref "U6") (pin "11") (pinfunction "MODE_11") (pintype "unspecified"))
    )
    (net (code "11") (name "GP6") (class "Default")
      (node (ref "MIKROBUS3") (pin "1") (pinfunction "AN_1") (pintype "unspecified"))
      (node (ref "U12") (pin "16") (pinfunction "GP6_16") (pintype "unspecified"))
    )
    (net (code "12") (name "GP7") (class "Default")
      (node (ref "MIKROBUS3") (pin "2") (pinfunction "RST_2") (pintype "unspecified"))
      (node (ref "U12") (pin "17") (pinfunction "GP7_17") (pintype "unspecified"))
    )
    (net (code "13") (name "GPA4") (class "Default")
      (node (ref "U13") (pin "1") (pinfunction "A_1") (pintype "unspecified"))
      (node (ref "U3") (pin "14") (pinfunction "SCSN_14") (pintype "unspecified"))
      (node (ref "U9") (pin "25") (pinfunction "GPA4_25") (pintype "bidirectional"))
    )
    (net (code "14") (name "GPA5") (class "Default")
      (node (ref "U13") (pin "2") (pinfunction "B_2") (pintype "unspecified"))
      (node (ref "U4") (pin "14") (pinfunction "SCSN_14") (pintype "unspecified"))
      (node (ref "U9") (pin "26") (pinfunction "GPA5_26") (pintype "bidirectional"))
    )
    (net (code "15") (name "IOref") (class "Default")
      (node (ref "C17") (pin "1") (pinfunction "1_1") (pintype "input"))
      (node (ref "C22") (pin "1") (pinfunction "1_1") (pintype "input"))
      (node (ref "C25") (pin "1") (pinfunction "1_1") (pintype "input"))
      (node (ref "C28") (pin "1") (pinfunction "1_1") (pintype "input"))
      (node (ref "C36") (pin "2") (pinfunction "2_2") (pintype "input"))
      (node (ref "J501") (pin "2") (pinfunction "2_2") (pintype "unspecified"))
      (node (ref "U1") (pin "5") (pinfunction "Vio_5") (pintype "unspecified"))
      (node (ref "U2") (pin "5") (pinfunction "Vio_5") (pintype "unspecified"))
      (node (ref "U3") (pin "5") (pinfunction "Vio_5") (pintype "unspecified"))
      (node (ref "U4") (pin "5") (pinfunction "Vio_5") (pintype "unspecified"))
    )
    (net (code "16") (name "Net-(C29-Pad2)") (class "Default")
      (node (ref "C29") (pin "2") (pinfunction "2_2") (pintype "input"))
      (node (ref "R10") (pin "1") (pinfunction "1_1") (pintype "unspecified"))
      (node (ref "R11") (pin "2") (pinfunction "2_2") (pintype "unspecified"))
    )
    (net (code "17") (name "Net-(C39-Pad1)") (class "Default")
      (node (ref "C39") (pin "1") (pinfunction "1_1") (pintype "input"))
      (node (ref "R12") (pin "2") (pinfunction "2_2") (pintype "unspecified"))
      (node (ref "R13") (pin "1") (pinfunction "1_1") (pintype "unspecified"))
    )
    (net (code "18") (name "Net-(D1-A)") (class "Default")
      (node (ref "D1") (pin "2") (pinfunction "A_2") (pintype "unspecified"))
      (node (ref "L1") (pin "2") (pinfunction "2_2") (pintype "unspecified"))
      (node (ref "U11") (pin "1") (pinfunction "SW_1") (pintype "unspecified"))
    )
    (net (code "19") (name "Net-(H1-Pad1)") (class "Default")
      (node (ref "H1") (pin "1") (pinfunction "1_1") (pintype "unspecified"))
      (node (ref "R10") (pin "2") (pinfunction "2_2") (pintype "unspecified"))
    )
    (net (code "20") (name "Net-(H2-Pad1)") (class "Default")
      (node (ref "H2") (pin "1") (pinfunction "1_1") (pintype "unspecified"))
      (node (ref "R11") (pin "1") (pinfunction "1_1") (pintype "unspecified"))
    )
    (net (code "21") (name "Net-(H3-Pad1)") (class "Default")
      (node (ref "H3") (pin "1") (pinfunction "1_1") (pintype "unspecified"))
      (node (ref "R13") (pin "2") (pinfunction "2_2") (pintype "unspecified"))
    )
    (net (code "22") (name "Net-(H4-Pad1)") (class "Default")
      (node (ref "H4") (pin "1") (pinfunction "1_1") (pintype "unspecified"))
      (node (ref "R12") (pin "1") (pinfunction "1_1") (pintype "unspecified"))
    )
    (net (code "23") (name "Net-(R14-Pad1)") (class "Default")
      (node (ref "R14") (pin "1") (pinfunction "1_1") (pintype "unspecified"))
      (node (ref "R15") (pin "2") (pinfunction "2_2") (pintype "unspecified"))
    )
    (net (code "24") (name "Net-(R16-Pad1)") (class "Default")
      (node (ref "R16") (pin "1") (pinfunction "1_1") (pintype "unspecified"))
      (node (ref "R17") (pin "2") (pinfunction "2_2") (pintype "unspecified"))
    )
    (net (code "25") (name "Net-(U1-INH)") (class "Default")
      (node (ref "U1") (pin "7") (pinfunction "INH_7") (pintype "unspecified"))
      (node (ref "U8") (pin "7") (pinfunction "GPB6_7") (pintype "bidirectional"))
    )
    (net (code "26") (name "Net-(U1-SDO)") (class "Default")
      (node (ref "R4") (pin "2") (pinfunction "2_2") (pintype "input"))
      (node (ref "U1") (pin "6") (pinfunction "SDO_6") (pintype "unspecified"))
    )
    (net (code "27") (name "Net-(U1-WAKE)") (class "Default")
      (node (ref "U1") (pin "9") (pinfunction "WAKE_9") (pintype "unspecified"))
      (node (ref "U8") (pin "8") (pinfunction "GPB7_8") (pintype "bidirectional"))
    )
    (net (code "28") (name "Net-(U3-INH)") (class "Default")
      (node (ref "U3") (pin "7") (pinfunction "INH_7") (pintype "unspecified"))
      (node (ref "U8") (pin "5") (pinfunction "GPB4_5") (pintype "bidirectional"))
    )
    (net (code "29") (name "Net-(U3-RxD)") (class "Default")
      (node (ref "U3") (pin "4") (pinfunction "RxD_4") (pintype "unspecified"))
      (node (ref "U5") (pin "2") (pinfunction "RXCAN_2") (pintype "unspecified"))
    )
    (net (code "30") (name "Net-(U3-SDO)") (class "Default")
      (node (ref "R5") (pin "2") (pinfunction "2_2") (pintype "input"))
      (node (ref "U3") (pin "6") (pinfunction "SDO_6") (pintype "unspecified"))
    )
    (net (code "31") (name "Net-(U3-TxD)") (class "Default")
      (node (ref "U3") (pin "1") (pinfunction "TxD_1") (pintype "unspecified"))
      (node (ref "U5") (pin "1") (pinfunction "TXCAN_1") (pintype "unspecified"))
    )
    (net (code "32") (name "Net-(U3-WAKE)") (class "Default")
      (node (ref "U3") (pin "9") (pinfunction "WAKE_9") (pintype "unspecified"))
      (node (ref "U8") (pin "6") (pinfunction "GPB5_6") (pintype "bidirectional"))
    )
    (net (code "33") (name "Net-(U4-INH)") (class "Default")
      (node (ref "U4") (pin "7") (pinfunction "INH_7") (pintype "unspecified"))
      (node (ref "U9") (pin "27") (pinfunction "GPA6_27") (pintype "bidirectional"))
    )
    (net (code "34") (name "Net-(U4-RxD)") (class "Default")
      (node (ref "U4") (pin "4") (pinfunction "RxD_4") (pintype "unspecified"))
      (node (ref "U6") (pin "19") (pinfunction "RX0_19") (pintype "unspecified"))
    )
    (net (code "35") (name "Net-(U4-SDO)") (class "Default")
      (node (ref "R6") (pin "2") (pinfunction "2_2") (pintype "input"))
      (node (ref "U4") (pin "6") (pinfunction "SDO_6") (pintype "unspecified"))
    )
    (net (code "36") (name "Net-(U4-TxD)") (class "Default")
      (node (ref "U4") (pin "1") (pinfunction "TxD_1") (pintype "unspecified"))
      (node (ref "U6") (pin "13") (pinfunction "TX0_13") (pintype "unspecified"))
    )
    (net (code "37") (name "Net-(U4-WAKE)") (class "Default")
      (node (ref "U4") (pin "9") (pinfunction "WAKE_9") (pintype "unspecified"))
      (node (ref "U9") (pin "28") (pinfunction "GPA7_28") (pintype "bidirectional"))
    )
    (net (code "38") (name "Net-(U5-CLKOUTSOF)") (class "Default")
      (node (ref "U5") (pin "3") (pinfunction "CLKOUTSOF_3") (pintype "unspecified"))
      (node (ref "U8") (pin "25") (pinfunction "GPA4_25") (pintype "bidirectional"))
    )
    (net (code "39") (name "Net-(U5-INT#)") (class "Default")
      (node (ref "U5") (pin "12") (pinfunction "INT#_12") (pintype "unspecified"))
      (node (ref "U8") (pin "26") (pinfunction "GPA5_26") (pintype "bidirectional"))
    )
    (net (code "40") (name "Net-(U5-OSC1)") (class "Default")
      (node (ref "C10") (pin "1") (pinfunction "1_1") (pintype "input"))
      (node (ref "U5") (pin "8") (pinfunction "OSC1_8") (pintype "unspecified"))
      (node (ref "X3") (pin "3") (pinfunction "3_3") (pintype "input"))
    )
    (net (code "41") (name "Net-(U5-OSC2)") (class "Default")
      (node (ref "C9") (pin "1") (pinfunction "1_1") (pintype "input"))
      (node (ref "U5") (pin "7") (pinfunction "OSC2_7") (pintype "unspecified"))
      (node (ref "X3") (pin "1") (pinfunction "1_1") (pintype "input"))
    )
    (net (code "42") (name "Net-(U5-RESET#)") (class "Default")
      (node (ref "U5") (pin "17") (pinfunction "RESET#_17") (pintype "unspecified"))
      (node (ref "U8") (pin "4") (pinfunction "GPB3_4") (pintype "bidirectional"))
    )
    (net (code "43") (name "Net-(U5-RX0BF#)") (class "Default")
      (node (ref "U5") (pin "11") (pinfunction "RX0BF#_11") (pintype "unspecified"))
      (node (ref "U8") (pin "27") (pinfunction "GPA6_27") (pintype "bidirectional"))
    )
    (net (code "44") (name "Net-(U5-RX1BF#)") (class "Default")
      (node (ref "U5") (pin "10") (pinfunction "RX1BF#_10") (pintype "unspecified"))
      (node (ref "U8") (pin "28") (pinfunction "GPA7_28") (pintype "bidirectional"))
    )
    (net (code "45") (name "Net-(U5-SO)") (class "Default")
      (node (ref "R8") (pin "2") (pinfunction "2_2") (pintype "input"))
      (node (ref "U5") (pin "15") (pinfunction "SO_15") (pintype "unspecified"))
    )
    (net (code "46") (name "Net-(U5-TX0RTS#)") (class "Default")
      (node (ref "U5") (pin "4") (pinfunction "TX0RTS#_4") (pintype "unspecified"))
      (node (ref "U8") (pin "1") (pinfunction "GPB0_1") (pintype "bidirectional"))
    )
    (net (code "47") (name "Net-(U5-TX1RTS#)") (class "Default")
      (node (ref "U5") (pin "5") (pinfunction "TX1RTS#_5") (pintype "unspecified"))
      (node (ref "U8") (pin "2") (pinfunction "GPB1_2") (pintype "bidirectional"))
    )
    (net (code "48") (name "Net-(U5-TX2RTS#)") (class "Default")
      (node (ref "U5") (pin "6") (pinfunction "TX2RTS#_6") (pintype "unspecified"))
      (node (ref "U8") (pin "3") (pinfunction "GPB2_3") (pintype "bidirectional"))
    )
    (net (code "49") (name "Net-(U6-AD0)") (class "Default")
      (node (ref "U6") (pin "23") (pinfunction "AD0_23") (pintype "unspecified"))
      (node (ref "U9") (pin "1") (pinfunction "GPB0_1") (pintype "bidirectional"))
    )
    (net (code "50") (name "Net-(U6-AD1)") (class "Default")
      (node (ref "U6") (pin "24") (pinfunction "AD1_24") (pintype "unspecified"))
      (node (ref "U9") (pin "2") (pinfunction "GPB1_2") (pintype "bidirectional"))
    )
    (net (code "51") (name "Net-(U6-AD2)") (class "Default")
      (node (ref "U6") (pin "25") (pinfunction "AD2_25") (pintype "unspecified"))
      (node (ref "U9") (pin "3") (pinfunction "GPB2_3") (pintype "bidirectional"))
    )
    (net (code "52") (name "Net-(U6-AD3)") (class "Default")
      (node (ref "U6") (pin "26") (pinfunction "AD3_26") (pintype "unspecified"))
      (node (ref "U9") (pin "4") (pinfunction "GPB3_4") (pintype "bidirectional"))
    )
    (net (code "53") (name "Net-(U6-AD4)") (class "Default")
      (node (ref "U6") (pin "27") (pinfunction "AD4_27") (pintype "unspecified"))
      (node (ref "U9") (pin "5") (pinfunction "GPB4_5") (pintype "bidirectional"))
    )
    (net (code "54") (name "Net-(U6-AD5)") (class "Default")
      (node (ref "U6") (pin "28") (pinfunction "AD5_28") (pintype "unspecified"))
      (node (ref "U9") (pin "6") (pinfunction "GPB5_6") (pintype "bidirectional"))
    )
    (net (code "55") (name "Net-(U6-AD6)") (class "Default")
      (node (ref "U6") (pin "1") (pinfunction "AD6_1") (pintype "unspecified"))
      (node (ref "U9") (pin "7") (pinfunction "GPB6_7") (pintype "bidirectional"))
    )
    (net (code "56") (name "Net-(U6-AD7)") (class "Default")
      (node (ref "U6") (pin "2") (pinfunction "AD7_2") (pintype "unspecified"))
      (node (ref "U9") (pin "8") (pinfunction "GPB7_8") (pintype "bidirectional"))
    )
    (net (code "57") (name "Net-(U6-ALE{slash}AS)") (class "Default")
      (node (ref "U6") (pin "3") (pinfunction "ALE/AS_3") (pintype "unspecified"))
      (node (ref "U9") (pin "21") (pinfunction "GPA0_21") (pintype "bidirectional"))
    )
    (net (code "58") (name "Net-(U6-CS#)") (class "Default")
      (node (ref "U6") (pin "4") (pinfunction "CS#_4") (pintype "unspecified"))
      (node (ref "U9") (pin "22") (pinfunction "GPA1_22") (pintype "bidirectional"))
    )
    (net (code "59") (name "Net-(U6-INT#)") (class "Default")
      (node (ref "U6") (pin "16") (pinfunction "INT#_16") (pintype "unspecified"))
      (node (ref "U8") (pin "23") (pinfunction "GPA2_23") (pintype "bidirectional"))
    )
    (net (code "60") (name "Net-(U6-RD#{slash}E)") (class "Default")
      (node (ref "U6") (pin "5") (pinfunction "RD#/E_5") (pintype "unspecified"))
      (node (ref "U9") (pin "23") (pinfunction "GPA2_23") (pintype "bidirectional"))
    )
    (net (code "61") (name "Net-(U6-WR#)") (class "Default")
      (node (ref "U6") (pin "6") (pinfunction "WR#_6") (pintype "unspecified"))
      (node (ref "U9") (pin "24") (pinfunction "GPA3_24") (pintype "bidirectional"))
    )
    (net (code "62") (name "Net-(U6-XTAL1)") (class "Default")
      (node (ref "C12") (pin "1") (pinfunction "1_1") (pintype "input"))
      (node (ref "U6") (pin "9") (pinfunction "XTAL1_9") (pintype "unspecified"))
      (node (ref "X1") (pin "1") (pinfunction "1_1") (pintype "input"))
    )
    (net (code "63") (name "Net-(U6-XTAL2)") (class "Default")
      (node (ref "C11") (pin "1") (pinfunction "1_1") (pintype "input"))
      (node (ref "U6") (pin "10") (pinfunction "XTAL2_10") (pintype "unspecified"))
      (node (ref "X1") (pin "3") (pinfunction "3_3") (pintype "input"))
    )
    (net (code "64") (name "Net-(U8-GPA0)") (class "Default")
      (node (ref "U8") (pin "21") (pinfunction "GPA0_21") (pintype "bidirectional"))
      (node (ref "U9") (pin "20") (pinfunction "INTA_20") (pintype "unspecified"))
    )
    (net (code "65") (name "Net-(U8-RESET#)") (class "Default")
      (node (ref "C14") (pin "2") (pinfunction "2_2") (pintype "input"))
      (node (ref "R2") (pin "1") (pinfunction "1_1") (pintype "input"))
      (node (ref "U8") (pin "18") (pinfunction "RESET#_18") (pintype "unspecified"))
    )
    (net (code "66") (name "Net-(U9-RESET#)") (class "Default")
      (node (ref "C8") (pin "2") (pinfunction "2_2") (pintype "input"))
      (node (ref "R1") (pin "1") (pinfunction "1_1") (pintype "input"))
      (node (ref "U9") (pin "18") (pinfunction "RESET#_18") (pintype "unspecified"))
    )
    (net (code "67") (name "Net-(U9-SO)") (class "Default")
      (node (ref "R7") (pin "2") (pinfunction "2_2") (pintype "input"))
      (node (ref "U9") (pin "14") (pinfunction "SO_14") (pintype "unspecified"))
    )
    (net (code "68") (name "Net-(U10-A)") (class "Default")
      (node (ref "U10") (pin "3") (pinfunction "A_3") (pintype "unspecified"))
      (node (ref "U2") (pin "6") (pinfunction "SDO/nINT_6") (pintype "unspecified"))
    )
    (net (code "69") (name "Net-(U10-Y0)") (class "Default")
      (node (ref "R20") (pin "1") (pinfunction "1_1") (pintype "input"))
      (node (ref "U10") (pin "6") (pinfunction "Y0_6") (pintype "unspecified"))
    )
    (net (code "70") (name "Net-(U10-Y1)") (class "Default")
      (node (ref "U10") (pin "4") (pinfunction "Y1_4") (pintype "unspecified"))
      (node (ref "U8") (pin "24") (pinfunction "GPA3_24") (pintype "bidirectional"))
    )
    (net (code "71") (name "Net-(U11-FB)") (class "Default")
      (node (ref "C32") (pin "1") (pinfunction "1_1") (pintype "unspecified"))
      (node (ref "R15") (pin "1") (pinfunction "1_1") (pintype "unspecified"))
      (node (ref "R16") (pin "2") (pinfunction "2_2") (pintype "unspecified"))
      (node (ref "U11") (pin "3") (pinfunction "FB_3") (pintype "unspecified"))
    )
    (net (code "72") (name "Net-(U12-GP4)") (class "Default")
      (node (ref "U12") (pin "14") (pinfunction "GP4_14") (pintype "unspecified"))
      (node (ref "U2") (pin "7") (pinfunction "INH/LIMP_7") (pintype "unspecified"))
    )
    (net (code "73") (name "Net-(U12-GP5)") (class "Default")
      (node (ref "U12") (pin "15") (pinfunction "GP5_15") (pintype "unspecified"))
      (node (ref "U2") (pin "9") (pinfunction "WAKE_9") (pintype "unspecified"))
    )
    (net (code "74") (name "Net-(U12-INT)") (class "Default")
      (node (ref "U12") (pin "8") (pinfunction "INT_8") (pintype "output"))
      (node (ref "U8") (pin "22") (pinfunction "GPA1_22") (pintype "bidirectional"))
    )
    (net (code "75") (name "Net-(U12-RESET#)") (class "Default")
      (node (ref "C16") (pin "2") (pinfunction "2_2") (pintype "input"))
      (node (ref "R3") (pin "1") (pinfunction "1_1") (pintype "input"))
      (node (ref "U12") (pin "6") (pinfunction "RESET#_6") (pintype "input"))
    )
    (net (code "76") (name "Net-(U13-Y)") (class "Default")
      (node (ref "U13") (pin "4") (pinfunction "Y_4") (pintype "unspecified"))
      (node (ref "U7") (pin "6") (pinfunction "E3_6") (pintype "unspecified"))
    )
    (net (code "77") (name "PA00") (class "Default")
      (node (ref "J503") (pin "3") (pinfunction "3_3") (pintype "unspecified"))
      (node (ref "MIKROBUS3") (pin "9") (pinfunction "PWM_9") (pintype "unspecified"))
    )
    (net (code "78") (name "PA02") (class "Default")
      (node (ref "J503") (pin "8") (pinfunction "8_8") (pintype "unspecified"))
      (node (ref "MIKROBUS1") (pin "9") (pinfunction "PWM_9") (pintype "unspecified"))
    )
    (net (code "79") (name "PA03") (class "Default")
      (node (ref "J500") (pin "9") (pinfunction "9_9") (pintype "unspecified"))
      (node (ref "MIKROBUS1") (pin "14") (pinfunction "SDA_14") (pintype "unspecified"))
      (node (ref "MIKROBUS2") (pin "14") (pinfunction "SDA_14") (pintype "unspecified"))
      (node (ref "MIKROBUS3") (pin "14") (pinfunction "SDA_14") (pintype "unspecified"))
      (node (ref "R19") (pin "1") (pinfunction "1_1") (pintype "unspecified"))
      (node (ref "U12") (pin "2") (pinfunction "SDA_2") (pintype "unspecified"))
      (node (ref "U8") (pin "13") (pinfunction "SDA_13") (pintype "unspecified"))
    )
    (net (code "80") (name "PA04") (class "Default")
      (node (ref "J500") (pin "10") (pinfunction "10_10") (pintype "unspecified"))
      (node (ref "MIKROBUS1") (pin "13") (pinfunction "SCL_13") (pintype "unspecified"))
      (node (ref "MIKROBUS2") (pin "13") (pinfunction "SCL_13") (pintype "unspecified"))
      (node (ref "MIKROBUS3") (pin "13") (pinfunction "SCL_13") (pintype "unspecified"))
      (node (ref "R18") (pin "1") (pinfunction "1_1") (pintype "unspecified"))
      (node (ref "U12") (pin "1") (pinfunction "SCL_1") (pintype "unspecified"))
      (node (ref "U8") (pin "12") (pinfunction "SCK_12") (pintype "unspecified"))
    )
    (net (code "81") (name "PA05") (class "Default")
      (node (ref "J500") (pin "1") (pinfunction "1_1") (pintype "unspecified"))
      (node (ref "MIKROBUS2") (pin "10") (pinfunction "INT_10") (pintype "unspecified"))
    )
    (net (code "82") (name "PA06") (class "Default")
      (node (ref "J503") (pin "4") (pinfunction "4_4") (pintype "unspecified"))
      (node (ref "MIKROBUS1") (pin "10") (pinfunction "INT_10") (pintype "unspecified"))
    )
    (net (code "83") (name "PA19") (class "Default")
      (node (ref "J502") (pin "3") (pinfunction "3_3") (pintype "unspecified"))
      (node (ref "MIKROBUS3") (pin "10") (pinfunction "INT_10") (pintype "unspecified"))
    )
    (net (code "84") (name "PA24") (class "Default")
      (node (ref "J507") (pin "26") (pinfunction "26_26") (pintype "unspecified"))
      (node (ref "R9") (pin "1") (pinfunction "1_1") (pintype "input"))
      (node (ref "U8") (pin "20") (pinfunction "INTA_20") (pintype "unspecified"))
    )
    (net (code "85") (name "PB00") (class "Default")
      (node (ref "J505") (pin "7") (pinfunction "7_7") (pintype "unspecified"))
      (node (ref "MIKROBUS2") (pin "11") (pinfunction "RX_11") (pintype "unspecified"))
    )
    (net (code "86") (name "PB01") (class "Default")
      (node (ref "J505") (pin "8") (pinfunction "8_8") (pintype "unspecified"))
      (node (ref "MIKROBUS2") (pin "12") (pinfunction "TX_12") (pintype "unspecified"))
    )
    (net (code "87") (name "PB02") (class "Default")
      (node (ref "J504") (pin "8") (pinfunction "8_8") (pintype "unspecified"))
      (node (ref "U1") (pin "1") (pinfunction "TxD_1") (pintype "unspecified"))
    )
    (net (code "88") (name "PB03") (class "Default")
      (node (ref "J504") (pin "7") (pinfunction "7_7") (pintype "unspecified"))
      (node (ref "U1") (pin "4") (pinfunction "RxD_4") (pintype "unspecified"))
    )
    (net (code "89") (name "PC12") (class "Default")
      (node (ref "J507") (pin "33") (pinfunction "33_33") (pintype "unspecified"))
      (node (ref "U2") (pin "4") (pinfunction "RxD_4") (pintype "unspecified"))
    )
    (net (code "90") (name "PC13") (class "Default")
      (node (ref "J502") (pin "5") (pinfunction "5_5") (pintype "unspecified"))
      (node (ref "MIKROBUS2") (pin "1") (pinfunction "AN_1") (pintype "unspecified"))
    )
    (net (code "91") (name "PC14") (class "Default")
      (node (ref "J507") (pin "34") (pinfunction "34_34") (pintype "unspecified"))
      (node (ref "U2") (pin "1") (pinfunction "TxD_1") (pintype "unspecified"))
    )
    (net (code "92") (name "PC19") (class "Default")
      (node (ref "J503") (pin "7") (pinfunction "7_7") (pintype "unspecified"))
      (node (ref "MIKROBUS2") (pin "9") (pinfunction "PWM_9") (pintype "unspecified"))
    )
    (net (code "93") (name "PC31") (class "Default")
      (node (ref "J502") (pin "2") (pinfunction "2_2") (pintype "unspecified"))
      (node (ref "MIKROBUS1") (pin "1") (pinfunction "AN_1") (pintype "unspecified"))
    )
    (net (code "94") (name "PD12") (class "Default")
      (node (ref "J400") (pin "24") (pinfunction "24_24") (pintype "unspecified"))
      (node (ref "U7") (pin "2") (pinfunction "A1_2") (pintype "unspecified"))
    )
    (net (code "95") (name "PD18") (class "Default")
      (node (ref "J505") (pin "3") (pinfunction "3_3") (pintype "unspecified"))
      (node (ref "MIKROBUS3") (pin "11") (pinfunction "RX_11") (pintype "unspecified"))
    )
    (net (code "96") (name "PD19") (class "Default")
      (node (ref "J505") (pin "4") (pinfunction "4_4") (pintype "unspecified"))
      (node (ref "MIKROBUS3") (pin "12") (pinfunction "TX_12") (pintype "unspecified"))
    )
    (net (code "97") (name "PD20") (class "Default")
      (node (ref "J500") (pin "5") (pinfunction "5_5") (pintype "unspecified"))
      (node (ref "MIKROBUS1") (pin "5") (pinfunction "MISO_5") (pintype "unspecified"))
      (node (ref "MIKROBUS2") (pin "5") (pinfunction "MISO_5") (pintype "unspecified"))
      (node (ref "MIKROBUS3") (pin "5") (pinfunction "MISO_5") (pintype "unspecified"))
      (node (ref "R20") (pin "2") (pinfunction "2_2") (pintype "input"))
      (node (ref "R4") (pin "1") (pinfunction "1_1") (pintype "input"))
      (node (ref "R5") (pin "1") (pinfunction "1_1") (pintype "input"))
      (node (ref "R6") (pin "1") (pinfunction "1_1") (pintype "input"))
      (node (ref "R7") (pin "1") (pinfunction "1_1") (pintype "input"))
      (node (ref "R8") (pin "1") (pinfunction "1_1") (pintype "input"))
    )
    (net (code "98") (name "PD21") (class "Default")
      (node (ref "J500") (pin "4") (pinfunction "4_4") (pintype "unspecified"))
      (node (ref "MIKROBUS1") (pin "6") (pinfunction "MOSI_6") (pintype "unspecified"))
      (node (ref "MIKROBUS2") (pin "6") (pinfunction "MOSI_6") (pintype "unspecified"))
      (node (ref "MIKROBUS3") (pin "6") (pinfunction "MOSI_6") (pintype "unspecified"))
      (node (ref "U1") (pin "11") (pinfunction "SDI_11") (pintype "unspecified"))
      (node (ref "U2") (pin "11") (pinfunction "SDI_11") (pintype "unspecified"))
      (node (ref "U3") (pin "11") (pinfunction "SDI_11") (pintype "unspecified"))
      (node (ref "U4") (pin "11") (pinfunction "SDI_11") (pintype "unspecified"))
      (node (ref "U5") (pin "14") (pinfunction "SI_14") (pintype "unspecified"))
      (node (ref "U9") (pin "13") (pinfunction "SI_13") (pintype "unspecified"))
    )
    (net (code "99") (name "PD22") (class "Default")
      (node (ref "J500") (pin "6") (pinfunction "6_6") (pintype "unspecified"))
      (node (ref "MIKROBUS1") (pin "4") (pinfunction "SCK_4") (pintype "unspecified"))
      (node (ref "MIKROBUS2") (pin "4") (pinfunction "SCK_4") (pintype "unspecified"))
      (node (ref "MIKROBUS3") (pin "4") (pinfunction "SCK_4") (pintype "unspecified"))
      (node (ref "U1") (pin "8") (pinfunction "SCLK_8") (pintype "unspecified"))
      (node (ref "U2") (pin "8") (pinfunction "SCLK_8") (pintype "unspecified"))
      (node (ref "U3") (pin "8") (pinfunction "SCK_8") (pintype "unspecified"))
      (node (ref "U4") (pin "8") (pinfunction "SCK_8") (pintype "unspecified"))
      (node (ref "U5") (pin "13") (pinfunction "SCK_13") (pintype "unspecified"))
      (node (ref "U9") (pin "12") (pinfunction "SCK_12") (pintype "unspecified"))
    )
    (net (code "100") (name "PD25") (class "Default")
      (node (ref "J400") (pin "12") (pinfunction "12_12") (pintype "unspecified"))
      (node (ref "U7") (pin "1") (pinfunction "A0_1") (pintype "unspecified"))
    )
    (net (code "101") (name "PD27") (class "Default")
      (node (ref "J400") (pin "26") (pinfunction "26_26") (pintype "unspecified"))
      (node (ref "U7") (pin "3") (pinfunction "A2_3") (pintype "unspecified"))
    )
    (net (code "102") (name "PD28") (class "Default")
      (node (ref "J503") (pin "1") (pinfunction "1_1") (pintype "unspecified"))
      (node (ref "MIKROBUS1") (pin "11") (pinfunction "RX_11") (pintype "unspecified"))
    )
    (net (code "103") (name "PD30") (class "Default")
      (node (ref "J503") (pin "2") (pinfunction "2_2") (pintype "unspecified"))
      (node (ref "MIKROBUS1") (pin "12") (pinfunction "TX_12") (pintype "unspecified"))
    )
    (net (code "104") (name "Y0") (class "Default")
      (node (ref "MIKROBUS1") (pin "3") (pinfunction "CS_3") (pintype "unspecified"))
      (node (ref "U7") (pin "15") (pinfunction "Y0#_15") (pintype "unspecified"))
    )
    (net (code "105") (name "Y1") (class "Default")
      (node (ref "MIKROBUS2") (pin "3") (pinfunction "CS_3") (pintype "unspecified"))
      (node (ref "U7") (pin "14") (pinfunction "Y1#_14") (pintype "unspecified"))
    )
    (net (code "106") (name "Y2") (class "Default")
      (node (ref "U5") (pin "16") (pinfunction "CS#_16") (pintype "unspecified"))
      (node (ref "U7") (pin "13") (pinfunction "Y2#_13") (pintype "unspecified"))
    )
    (net (code "107") (name "Y3") (class "Default")
      (node (ref "U7") (pin "12") (pinfunction "Y3#_12") (pintype "unspecified"))
      (node (ref "U9") (pin "11") (pinfunction "CS#_11") (pintype "unspecified"))
    )
    (net (code "108") (name "Y4") (class "Default")
      (node (ref "U1") (pin "14") (pinfunction "nCS_14") (pintype "unspecified"))
      (node (ref "U7") (pin "11") (pinfunction "Y4#_11") (pintype "unspecified"))
    )
    (net (code "109") (name "Y5") (class "Default")
      (node (ref "U10") (pin "1") (pinfunction "S_1") (pintype "unspecified"))
      (node (ref "U2") (pin "14") (pinfunction "nCS_14") (pintype "unspecified"))
      (node (ref "U7") (pin "10") (pinfunction "Y5#_10") (pintype "unspecified"))
    )
    (net (code "110") (name "Y6") (class "Default")
      (node (ref "MIKROBUS3") (pin "3") (pinfunction "CS_3") (pintype "unspecified"))
      (node (ref "U7") (pin "9") (pinfunction "Y6#_9") (pintype "unspecified"))
    )
    (net (code "111") (name "unconnected-(J400-Pad1)") (class "Default")
      (node (ref "J400") (pin "1") (pinfunction "1_1") (pintype "unspecified+no_connect"))
    )
    (net (code "112") (name "unconnected-(J400-Pad3)") (class "Default")
      (node (ref "J400") (pin "3") (pinfunction "3_3") (pintype "unspecified+no_connect"))
    )
    (net (code "113") (name "unconnected-(J400-Pad5)") (class "Default")
      (node (ref "J400") (pin "5") (pinfunction "5_5") (pintype "unspecified+no_connect"))
    )
    (net (code "114") (name "unconnected-(J400-Pad6)") (class "Default")
      (node (ref "J400") (pin "6") (pinfunction "6_6") (pintype "unspecified+no_connect"))
    )
    (net (code "115") (name "unconnected-(J400-Pad7)") (class "Default")
      (node (ref "J400") (pin "7") (pinfunction "7_7") (pintype "unspecified+no_connect"))
    )
    (net (code "116") (name "unconnected-(J400-Pad8)") (class "Default")
      (node (ref "J400") (pin "8") (pinfunction "8_8") (pintype "unspecified+no_connect"))
    )
    (net (code "117") (name "unconnected-(J400-Pad10)") (class "Default")
      (node (ref "J400") (pin "10") (pinfunction "10_10") (pintype "unspecified+no_connect"))
    )
    (net (code "118") (name "unconnected-(J400-Pad14)") (class "Default")
      (node (ref "J400") (pin "14") (pinfunction "14_14") (pintype "unspecified+no_connect"))
    )
    (net (code "119") (name "unconnected-(J400-Pad16)") (class "Default")
      (node (ref "J400") (pin "16") (pinfunction "16_16") (pintype "unspecified+no_connect"))
    )
    (net (code "120") (name "unconnected-(J400-Pad18)") (class "Default")
      (node (ref "J400") (pin "18") (pinfunction "18_18") (pintype "unspecified+no_connect"))
    )
    (net (code "121") (name "unconnected-(J400-Pad19)") (class "Default")
      (node (ref "J400") (pin "19") (pinfunction "19_19") (pintype "unspecified+no_connect"))
    )
    (net (code "122") (name "unconnected-(J400-Pad20)") (class "Default")
      (node (ref "J400") (pin "20") (pinfunction "20_20") (pintype "unspecified+no_connect"))
    )
    (net (code "123") (name "unconnected-(J400-Pad21)") (class "Default")
      (node (ref "J400") (pin "21") (pinfunction "21_21") (pintype "unspecified+no_connect"))
    )
    (net (code "124") (name "unconnected-(J400-Pad22)") (class "Default")
      (node (ref "J400") (pin "22") (pinfunction "22_22") (pintype "unspecified+no_connect"))
    )
    (net (code "125") (name "unconnected-(J400-Pad23)") (class "Default")
      (node (ref "J400") (pin "23") (pinfunction "23_23") (pintype "unspecified+no_connect"))
    )
    (net (code "126") (name "unconnected-(J400-Pad25)") (class "Default")
      (node (ref "J400") (pin "25") (pinfunction "25_25") (pintype "unspecified+no_connect"))
    )
    (net (code "127") (name "unconnected-(J400-Pad27)") (class "Default")
      (node (ref "J400") (pin "27") (pinfunction "27_27") (pintype "unspecified+no_connect"))
    )
    (net (code "128") (name "unconnected-(J400-Pad28)") (class "Default")
      (node (ref "J400") (pin "28") (pinfunction "28_28") (pintype "unspecified+no_connect"))
    )
    (net (code "129") (name "unconnected-(J400-Pad29)") (class "Default")
      (node (ref "J400") (pin "29") (pinfunction "29_29") (pintype "unspecified+no_connect"))
    )
    (net (code "130") (name "unconnected-(J500-Pad2)") (class "Default")
      (node (ref "J500") (pin "2") (pinfunction "2_2") (pintype "unspecified+no_connect"))
    )
    (net (code "131") (name "unconnected-(J500-Pad3)") (class "Default")
      (node (ref "J500") (pin "3") (pinfunction "3_3") (pintype "unspecified+no_connect"))
    )
    (net (code "132") (name "unconnected-(J500-Pad8)") (class "Default")
      (node (ref "J500") (pin "8") (pinfunction "8_8") (pintype "unspecified+no_connect"))
    )
    (net (code "133") (name "unconnected-(J501-Pad1)") (class "Default")
      (node (ref "J501") (pin "1") (pinfunction "1_1") (pintype "unspecified+no_connect"))
    )
    (net (code "134") (name "unconnected-(J501-Pad3)") (class "Default")
      (node (ref "J501") (pin "3") (pinfunction "3_3") (pintype "unspecified+no_connect"))
    )
    (net (code "135") (name "unconnected-(J501-Pad8)") (class "Default")
      (node (ref "J501") (pin "8") (pinfunction "8_8") (pintype "unspecified+no_connect"))
    )
    (net (code "136") (name "unconnected-(J502-Pad1)") (class "Default")
      (node (ref "J502") (pin "1") (pinfunction "1_1") (pintype "unspecified+no_connect"))
    )
    (net (code "137") (name "unconnected-(J502-Pad4)") (class "Default")
      (node (ref "J502") (pin "4") (pinfunction "4_4") (pintype "unspecified+no_connect"))
    )
    (net (code "138") (name "unconnected-(J502-Pad6)") (class "Default")
      (node (ref "J502") (pin "6") (pinfunction "6_6") (pintype "unspecified+no_connect"))
    )
    (net (code "139") (name "unconnected-(J502-Pad7)") (class "Default")
      (node (ref "J502") (pin "7") (pinfunction "7_7") (pintype "unspecified+no_connect"))
    )
    (net (code "140") (name "unconnected-(J502-Pad8)") (class "Default")
      (node (ref "J502") (pin "8") (pinfunction "8_8") (pintype "unspecified+no_connect"))
    )
    (net (code "141") (name "unconnected-(J503-Pad5)") (class "Default")
      (node (ref "J503") (pin "5") (pinfunction "5_5") (pintype "unspecified+no_connect"))
    )
    (net (code "142") (name "unconnected-(J503-Pad6)") (class "Default")
      (node (ref "J503") (pin "6") (pinfunction "6_6") (pintype "unspecified+no_connect"))
    )
    (net (code "143") (name "unconnected-(J504-Pad1)") (class "Default")
      (node (ref "J504") (pin "1") (pinfunction "1_1") (pintype "unspecified+no_connect"))
    )
    (net (code "144") (name "unconnected-(J504-Pad2)") (class "Default")
      (node (ref "J504") (pin "2") (pinfunction "2_2") (pintype "unspecified+no_connect"))
    )
    (net (code "145") (name "unconnected-(J504-Pad3)") (class "Default")
      (node (ref "J504") (pin "3") (pinfunction "3_3") (pintype "unspecified+no_connect"))
    )
    (net (code "146") (name "unconnected-(J504-Pad4)") (class "Default")
      (node (ref "J504") (pin "4") (pinfunction "4_4") (pintype "unspecified+no_connect"))
    )
    (net (code "147") (name "unconnected-(J504-Pad5)") (class "Default")
      (node (ref "J504") (pin "5") (pinfunction "5_5") (pintype "unspecified+no_connect"))
    )
    (net (code "148") (name "unconnected-(J504-Pad6)") (class "Default")
      (node (ref "J504") (pin "6") (pinfunction "6_6") (pintype "unspecified+no_connect"))
    )
    (net (code "149") (name "unconnected-(J505-Pad1)") (class "Default")
      (node (ref "J505") (pin "1") (pinfunction "1_1") (pintype "unspecified+no_connect"))
    )
    (net (code "150") (name "unconnected-(J505-Pad2)") (class "Default")
      (node (ref "J505") (pin "2") (pinfunction "2_2") (pintype "unspecified+no_connect"))
    )
    (net (code "151") (name "unconnected-(J505-Pad5)") (class "Default")
      (node (ref "J505") (pin "5") (pinfunction "5_5") (pintype "unspecified+no_connect"))
    )
    (net (code "152") (name "unconnected-(J505-Pad6)") (class "Default")
      (node (ref "J505") (pin "6") (pinfunction "6_6") (pintype "unspecified+no_connect"))
    )
    (net (code "153") (name "unconnected-(J507-Pad1)") (class "Default")
      (node (ref "J507") (pin "1") (pinfunction "1_1") (pintype "unspecified+no_connect"))
    )
    (net (code "154") (name "unconnected-(J507-Pad2)") (class "Default")
      (node (ref "J507") (pin "2") (pinfunction "2_2") (pintype "unspecified+no_connect"))
    )
    (net (code "155") (name "unconnected-(J507-Pad3)") (class "Default")
      (node (ref "J507") (pin "3") (pinfunction "3_3") (pintype "unspecified+no_connect"))
    )
    (net (code "156") (name "unconnected-(J507-Pad4)") (class "Default")
      (node (ref "J507") (pin "4") (pinfunction "4_4") (pintype "unspecified+no_connect"))
    )
    (net (code "157") (name "unconnected-(J507-Pad5)") (class "Default")
      (node (ref "J507") (pin "5") (pinfunction "5_5") (pintype "unspecified+no_connect"))
    )
    (net (code "158") (name "unconnected-(J507-Pad6)") (class "Default")
      (node (ref "J507") (pin "6") (pinfunction "6_6") (pintype "unspecified+no_connect"))
    )
    (net (code "159") (name "unconnected-(J507-Pad7)") (class "Default")
      (node (ref "J507") (pin "7") (pinfunction "7_7") (pintype "unspecified+no_connect"))
    )
    (net (code "160") (name "unconnected-(J507-Pad8)") (class "Default")
      (node (ref "J507") (pin "8") (pinfunction "8_8") (pintype "unspecified+no_connect"))
    )
    (net (code "161") (name "unconnected-(J507-Pad9)") (class "Default")
      (node (ref "J507") (pin "9") (pinfunction "9_9") (pintype "unspecified+no_connect"))
    )
    (net (code "162") (name "unconnected-(J507-Pad10)") (class "Default")
      (node (ref "J507") (pin "10") (pinfunction "10_10") (pintype "unspecified+no_connect"))
    )
    (net (code "163") (name "unconnected-(J507-Pad11)") (class "Default")
      (node (ref "J507") (pin "11") (pinfunction "11_11") (pintype "unspecified+no_connect"))
    )
    (net (code "164") (name "unconnected-(J507-Pad12)") (class "Default")
      (node (ref "J507") (pin "12") (pinfunction "12_12") (pintype "unspecified+no_connect"))
    )
    (net (code "165") (name "unconnected-(J507-Pad13)") (class "Default")
      (node (ref "J507") (pin "13") (pinfunction "13_13") (pintype "unspecified+no_connect"))
    )
    (net (code "166") (name "unconnected-(J507-Pad14)") (class "Default")
      (node (ref "J507") (pin "14") (pinfunction "14_14") (pintype "unspecified+no_connect"))
    )
    (net (code "167") (name "unconnected-(J507-Pad15)") (class "Default")
      (node (ref "J507") (pin "15") (pinfunction "15_15") (pintype "unspecified+no_connect"))
    )
    (net (code "168") (name "unconnected-(J507-Pad16)") (class "Default")
      (node (ref "J507") (pin "16") (pinfunction "16_16") (pintype "unspecified+no_connect"))
    )
    (net (code "169") (name "unconnected-(J507-Pad17)") (class "Default")
      (node (ref "J507") (pin "17") (pinfunction "17_17") (pintype "unspecified+no_connect"))
    )
    (net (code "170") (name "unconnected-(J507-Pad18)") (class "Default")
      (node (ref "J507") (pin "18") (pinfunction "18_18") (pintype "unspecified+no_connect"))
    )
    (net (code "171") (name "unconnected-(J507-Pad19)") (class "Default")
      (node (ref "J507") (pin "19") (pinfunction "19_19") (pintype "unspecified+no_connect"))
    )
    (net (code "172") (name "unconnected-(J507-Pad20)") (class "Default")
      (node (ref "J507") (pin "20") (pinfunction "20_20") (pintype "unspecified+no_connect"))
    )
    (net (code "173") (name "unconnected-(J507-Pad21)") (class "Default")
      (node (ref "J507") (pin "21") (pinfunction "21_21") (pintype "unspecified+no_connect"))
    )
    (net (code "174") (name "unconnected-(J507-Pad22)") (class "Default")
      (node (ref "J507") (pin "22") (pinfunction "22_22") (pintype "unspecified+no_connect"))
    )
    (net (code "175") (name "unconnected-(J507-Pad23)") (class "Default")
      (node (ref "J507") (pin "23") (pinfunction "23_23") (pintype "unspecified+no_connect"))
    )
    (net (code "176") (name "unconnected-(J507-Pad24)") (class "Default")
      (node (ref "J507") (pin "24") (pinfunction "24_24") (pintype "unspecified+no_connect"))
    )
    (net (code "177") (name "unconnected-(J507-Pad25)") (class "Default")
      (node (ref "J507") (pin "25") (pinfunction "25_25") (pintype "unspecified+no_connect"))
    )
    (net (code "178") (name "unconnected-(J507-Pad27)") (class "Default")
      (node (ref "J507") (pin "27") (pinfunction "27_27") (pintype "unspecified+no_connect"))
    )
    (net (code "179") (name "unconnected-(J507-Pad28)") (class "Default")
      (node (ref "J507") (pin "28") (pinfunction "28_28") (pintype "unspecified+no_connect"))
    )
    (net (code "180") (name "unconnected-(J507-Pad29)") (class "Default")
      (node (ref "J507") (pin "29") (pinfunction "29_29") (pintype "unspecified+no_connect"))
    )
    (net (code "181") (name "unconnected-(J507-Pad30)") (class "Default")
      (node (ref "J507") (pin "30") (pinfunction "30_30") (pintype "unspecified+no_connect"))
    )
    (net (code "182") (name "unconnected-(J507-Pad31)") (class "Default")
      (node (ref "J507") (pin "31") (pinfunction "31_31") (pintype "unspecified+no_connect"))
    )
    (net (code "183") (name "unconnected-(J507-Pad32)") (class "Default")
      (node (ref "J507") (pin "32") (pinfunction "32_32") (pintype "unspecified+no_connect"))
    )
    (net (code "184") (name "unconnected-(U6-CLKOUT-Pad7)") (class "Default")
      (node (ref "U6") (pin "7") (pinfunction "CLKOUT_7") (pintype "unspecified+no_connect"))
    )
    (net (code "185") (name "unconnected-(U6-TX1-Pad14)") (class "Default")
      (node (ref "U6") (pin "14") (pinfunction "TX1_14") (pintype "unspecified+no_connect"))
    )
    (net (code "186") (name "unconnected-(U7-Y7#-Pad7)") (class "Default")
      (node (ref "U7") (pin "7") (pinfunction "Y7#_7") (pintype "unspecified+no_connect"))
    )
    (net (code "187") (name "unconnected-(U8-INTB-Pad19)") (class "Default")
      (node (ref "U8") (pin "19") (pinfunction "INTB_19") (pintype "unspecified+no_connect"))
    )
    (net (code "188") (name "unconnected-(U8-NC-Pad11)") (class "Default")
      (node (ref "U8") (pin "11") (pinfunction "NC_11") (pintype "unspecified+no_connect"))
    )
    (net (code "189") (name "unconnected-(U8-NC-Pad14)") (class "Default")
      (node (ref "U8") (pin "14") (pinfunction "NC_14") (pintype "unspecified+no_connect"))
    )
    (net (code "190") (name "unconnected-(U9-INTB-Pad19)") (class "Default")
      (node (ref "U9") (pin "19") (pinfunction "INTB_19") (pintype "unspecified+no_connect"))
    )
    (net (code "191") (name "unconnected-(U12-NC-Pad7)") (class "Default")
      (node (ref "U12") (pin "7") (pinfunction "NC_7") (pintype "output+no_connect"))
    )
    (net (code "192") (name "unconnected-(X1-GND-Pad2)") (class "Default")
      (node (ref "X1") (pin "2") (pinfunction "GND_2") (pintype "input+no_connect"))
    )
    (net (code "193") (name "unconnected-(X1-GND-Pad4)") (class "Default")
      (node (ref "X1") (pin "4") (pinfunction "GND_4") (pintype "input+no_connect"))
    )
    (net (code "194") (name "unconnected-(X3-GND-Pad2)") (class "Default")
      (node (ref "X3") (pin "2") (pinfunction "GND_2") (pintype "input+no_connect"))
    )
    (net (code "195") (name "unconnected-(X3-GND-Pad4)") (class "Default")
      (node (ref "X3") (pin "4") (pinfunction "GND_4") (pintype "input+no_connect"))
    )
  )
)
